# mainboard_v03_eurobot2014_r1.net
KiCad netlist of a schematic drawn in EAGLE
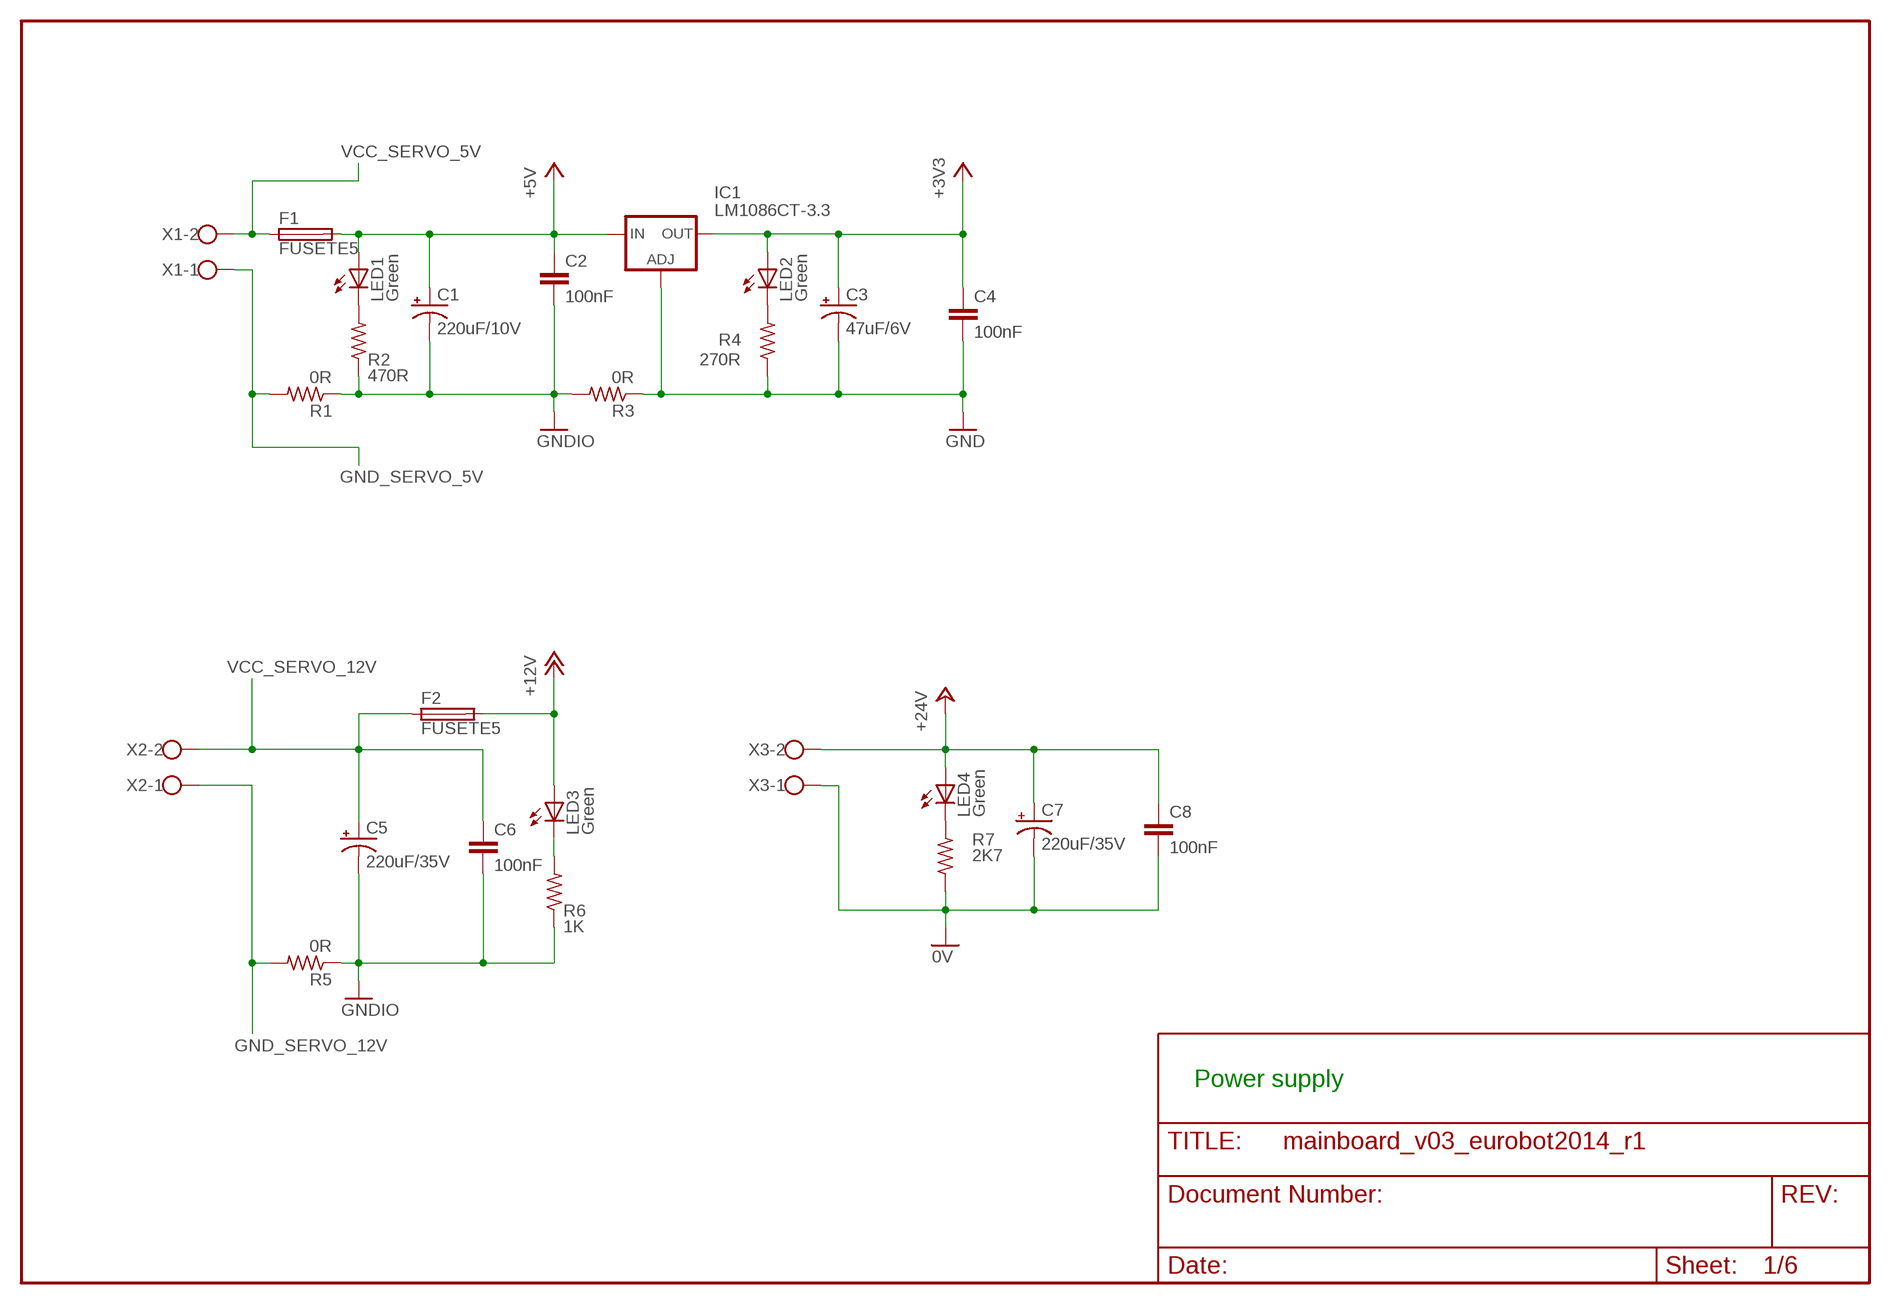
[diagram p0: schematic, sheet 1]
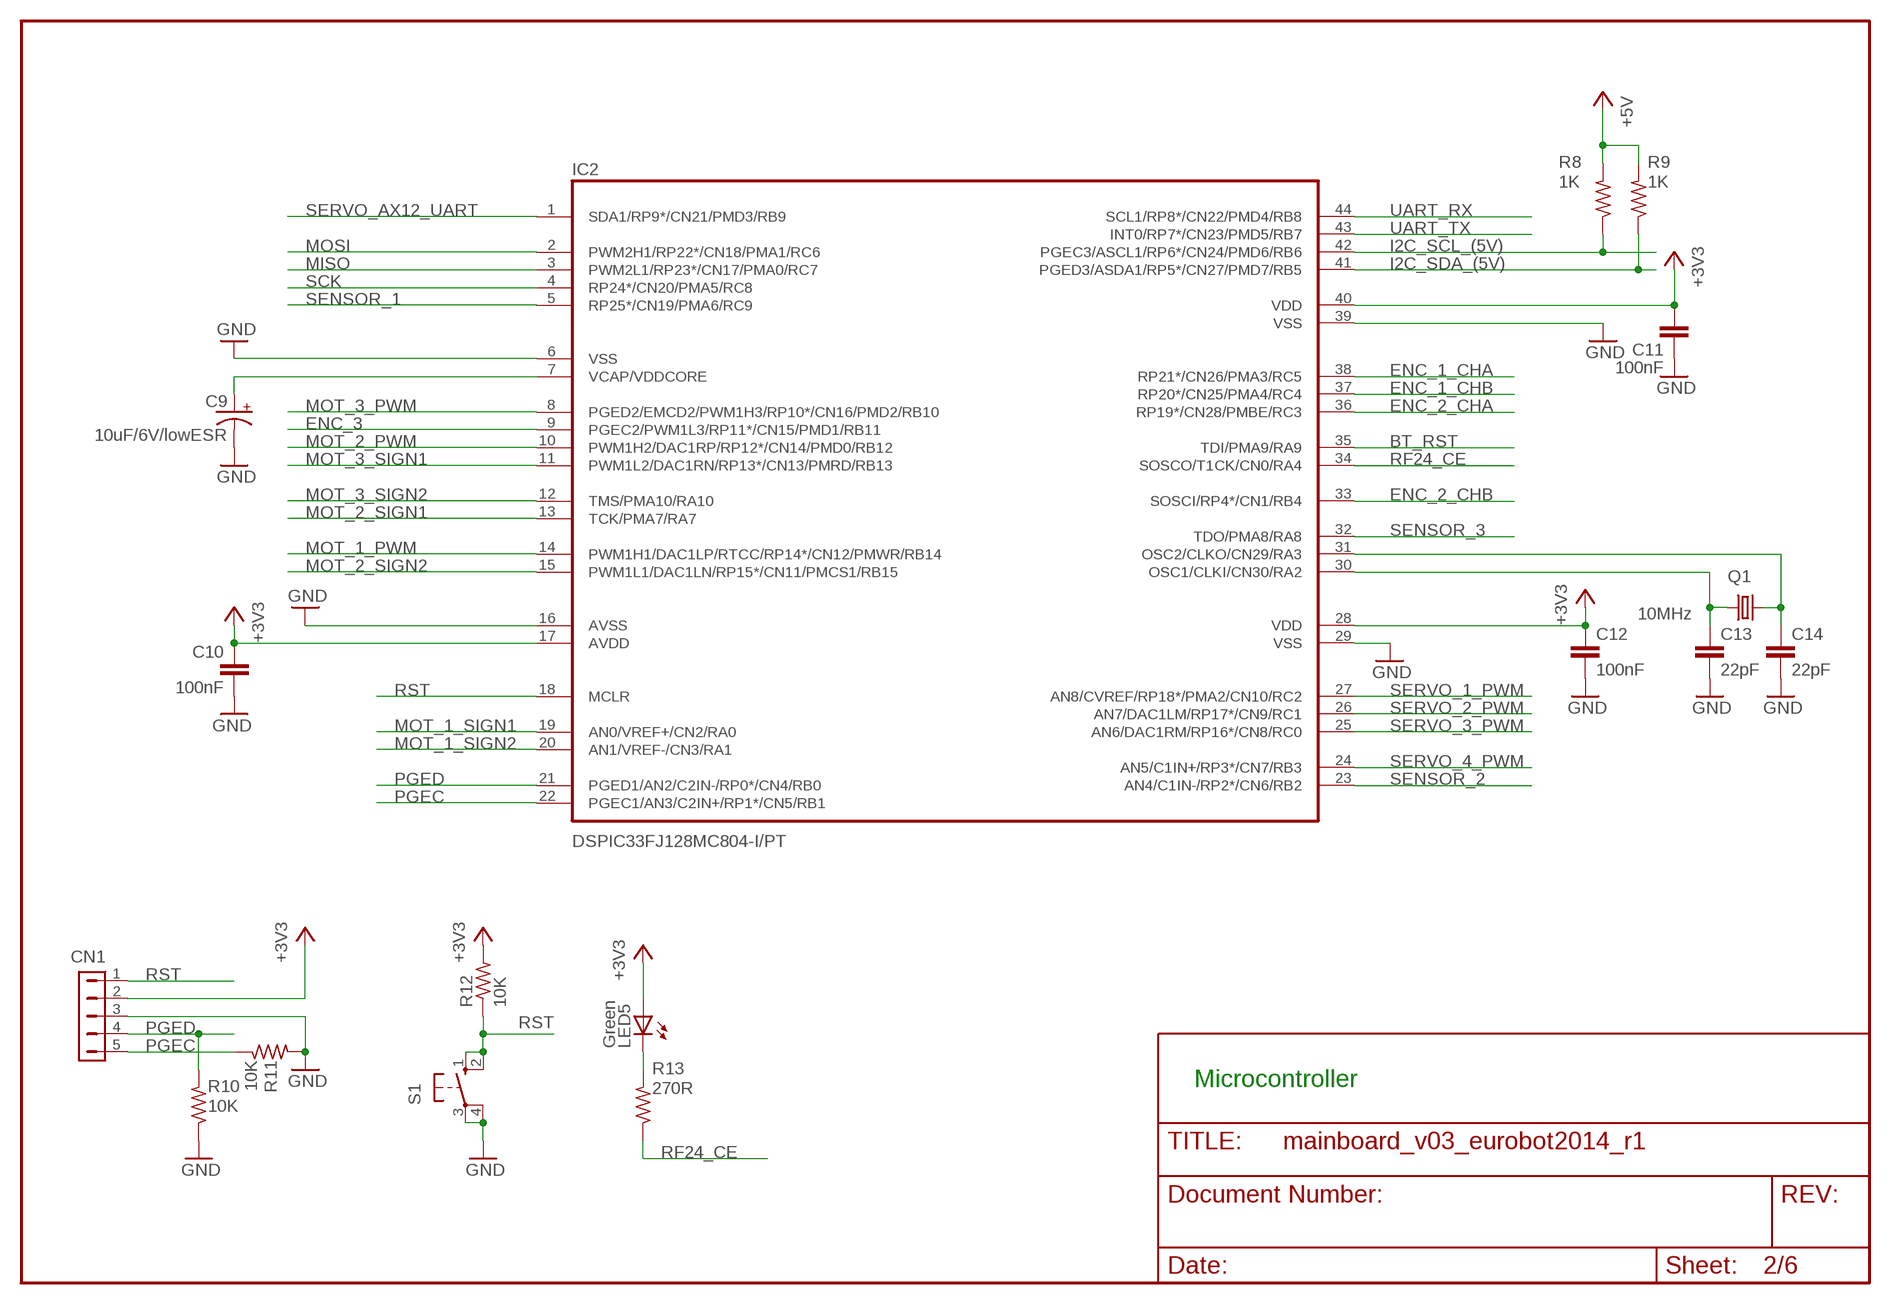
[diagram p1: schematic, sheet 2]
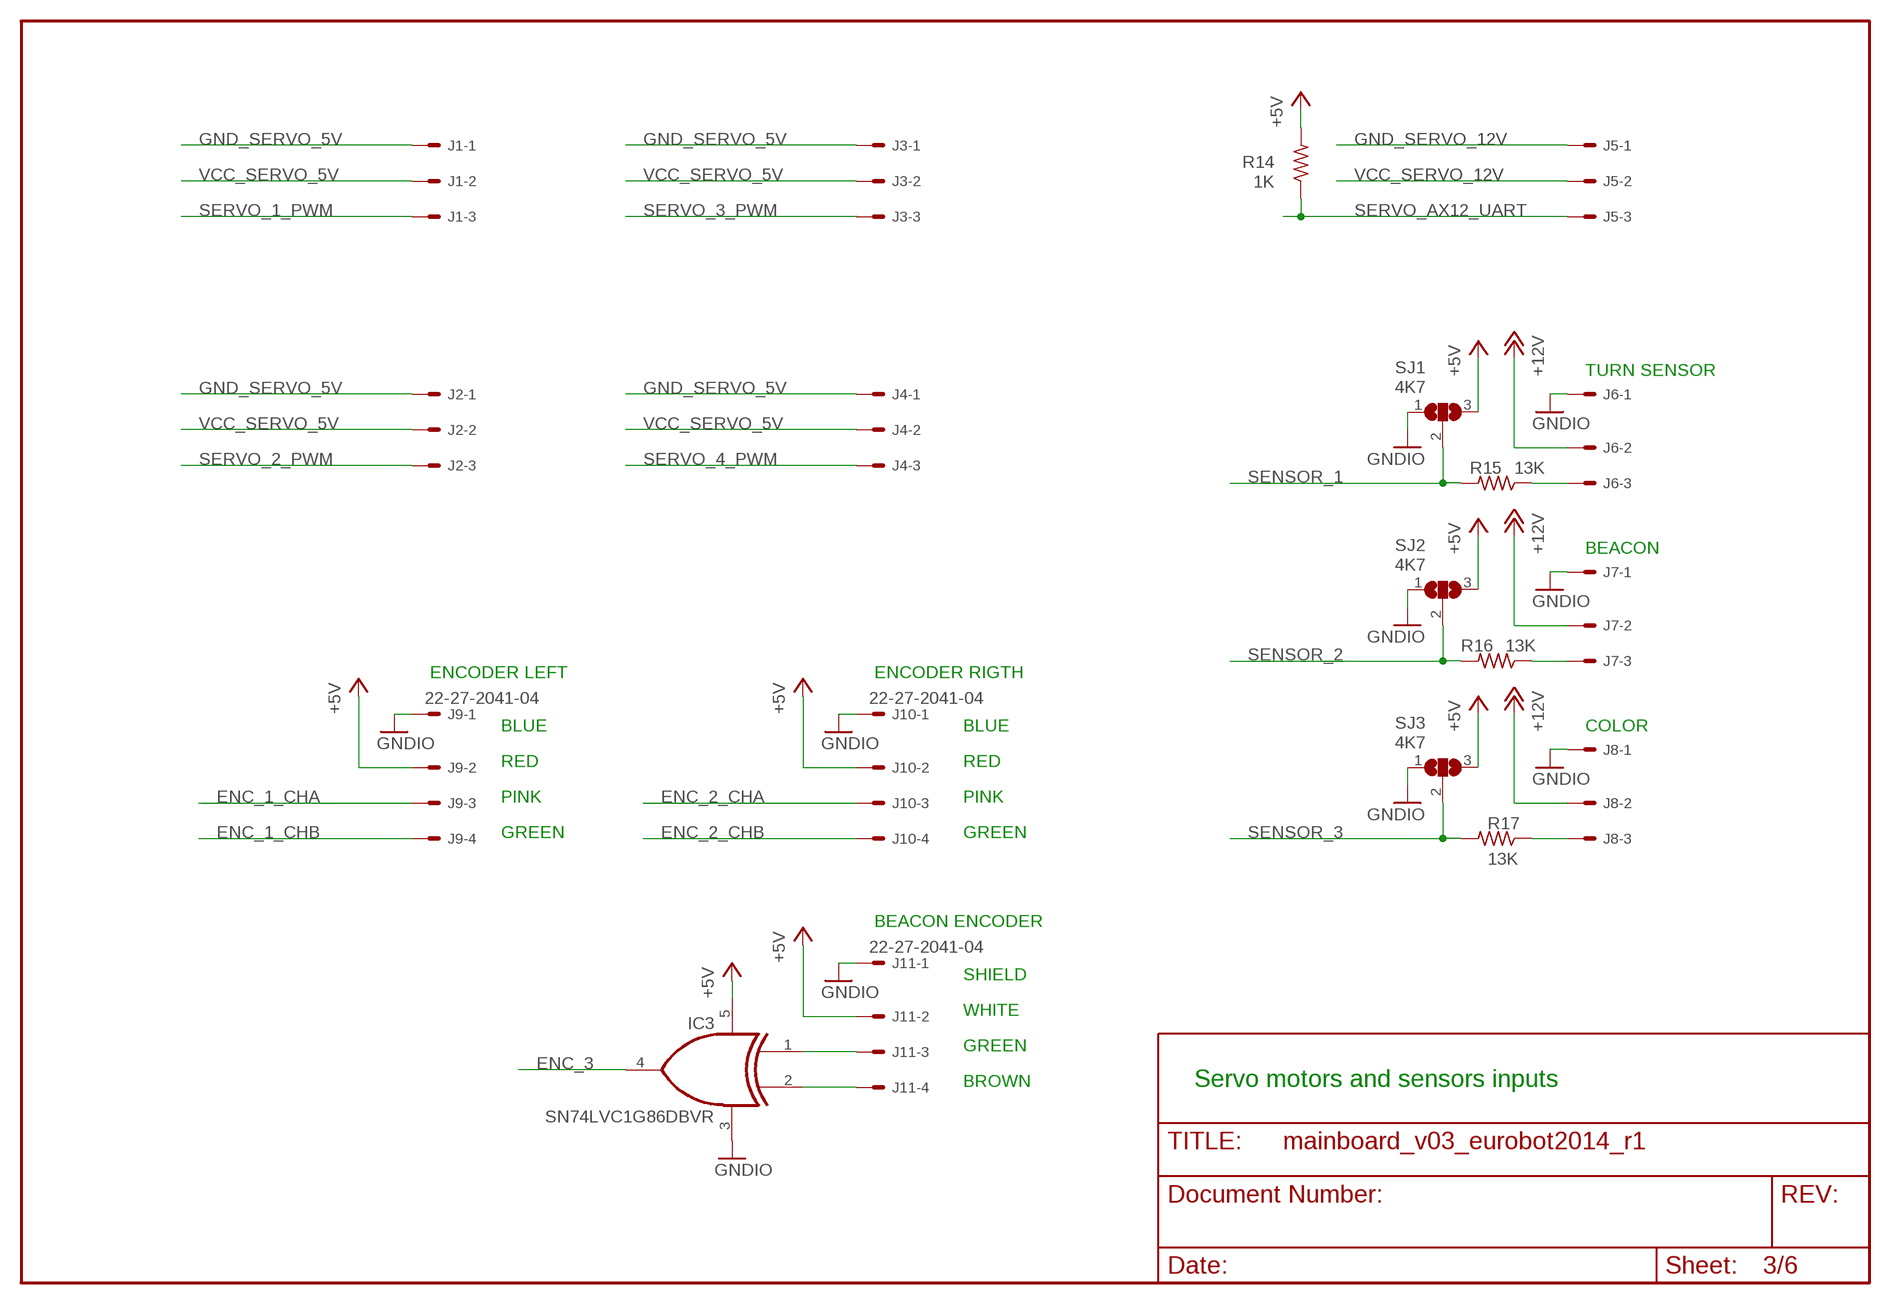
[diagram p2: schematic, sheet 3]
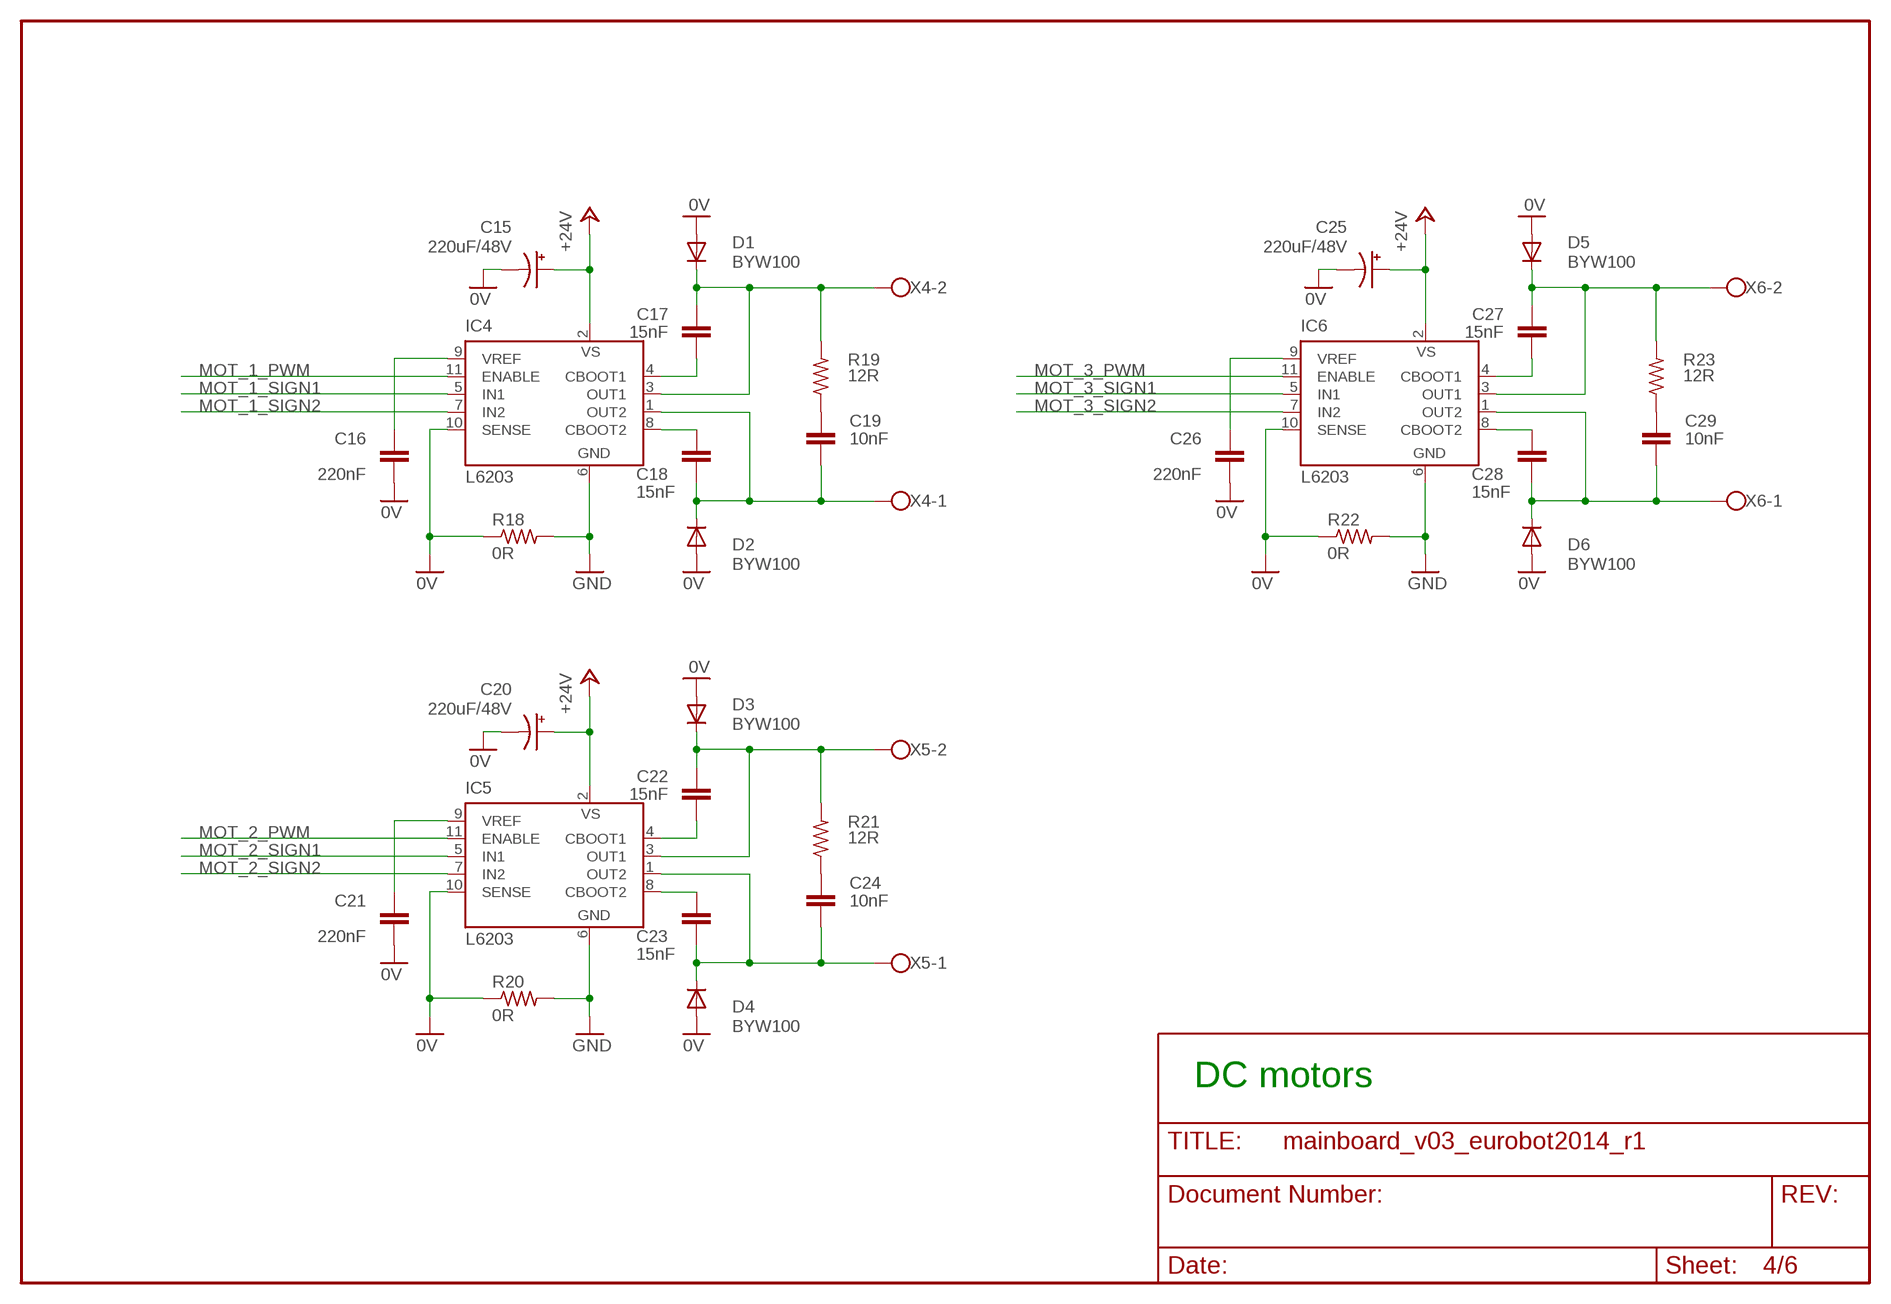
[diagram p3: schematic, sheet 4]
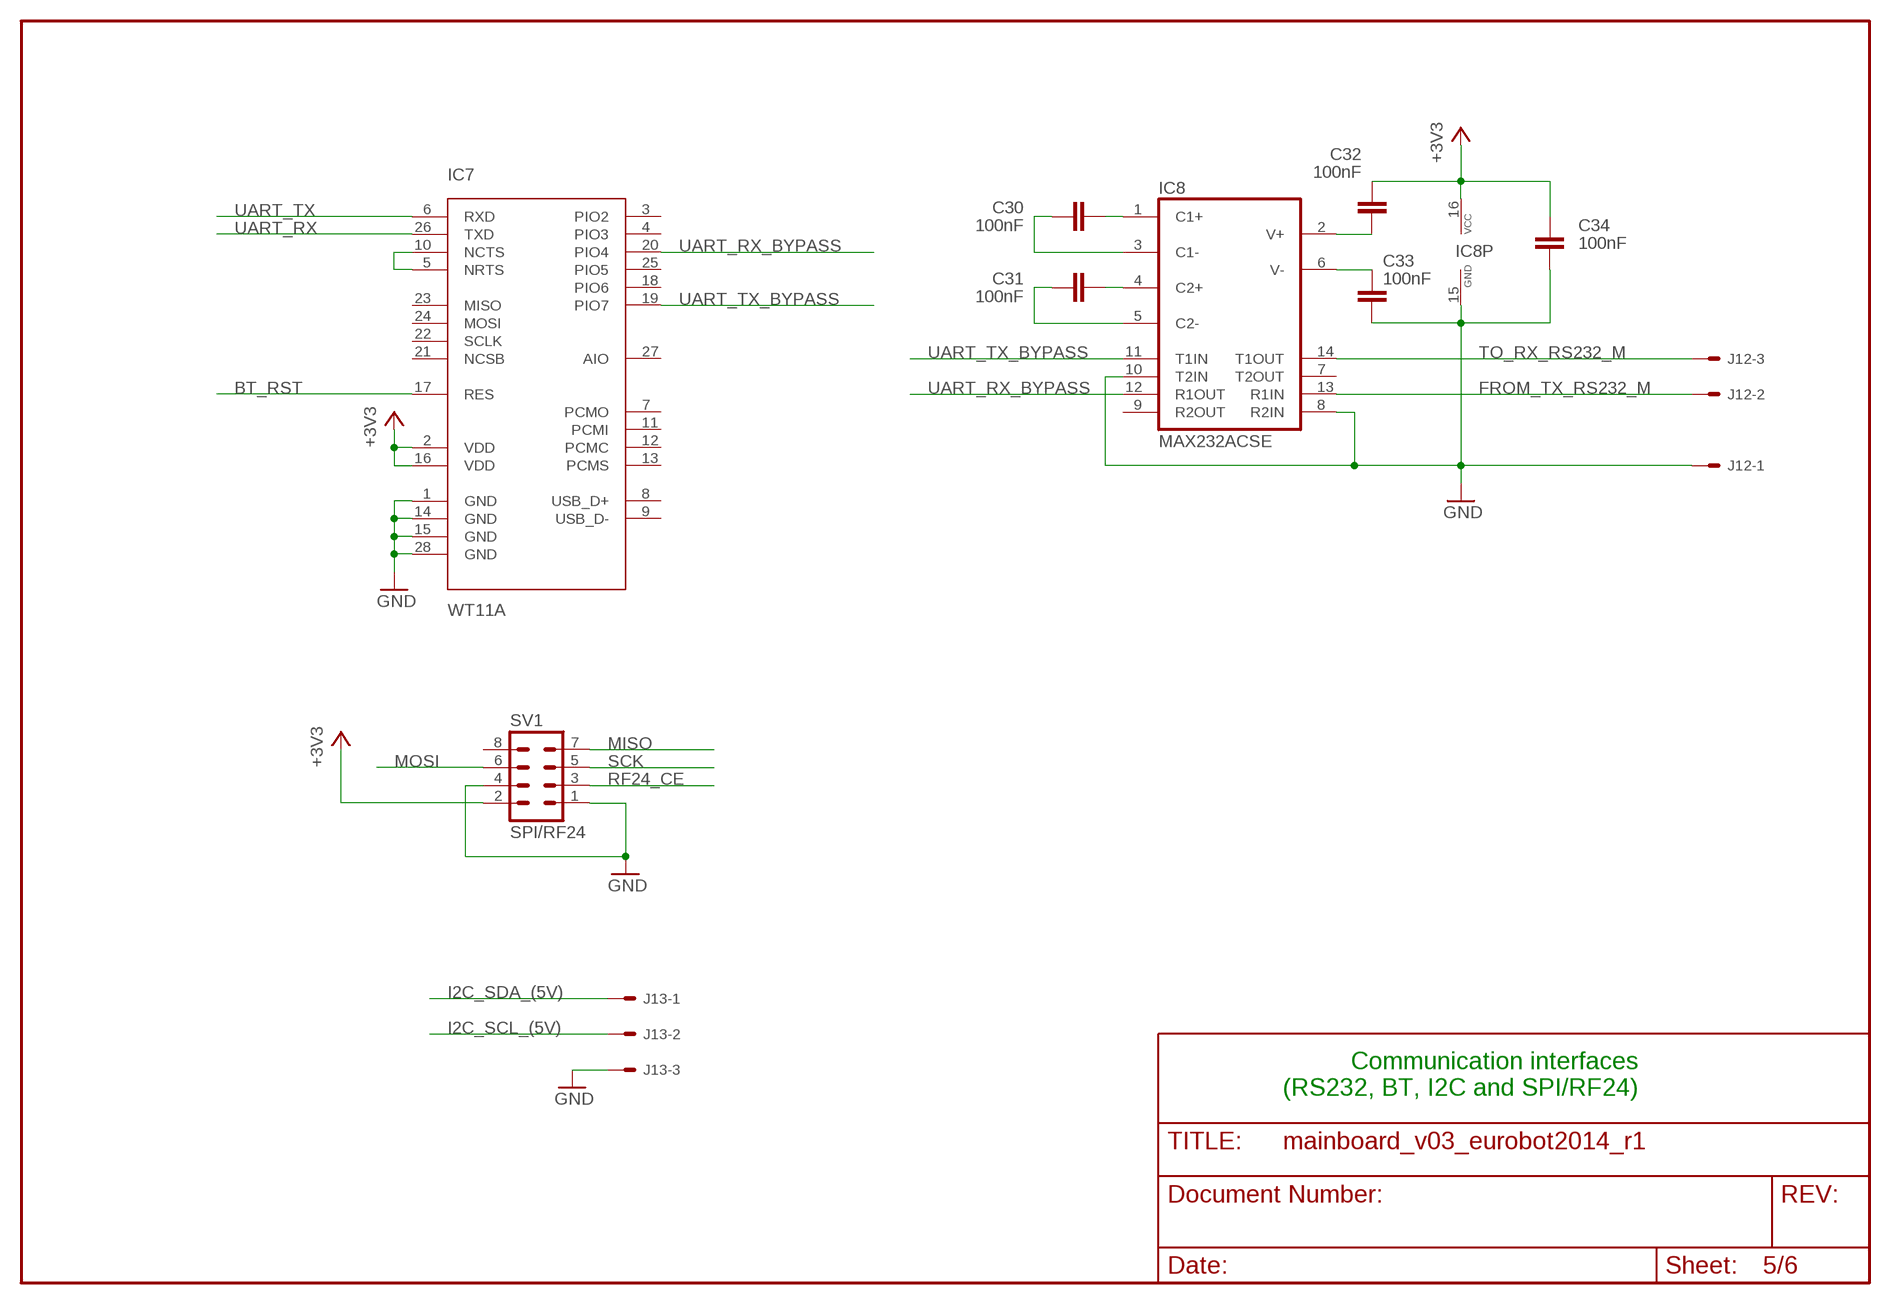
[diagram p4: schematic, sheet 5]
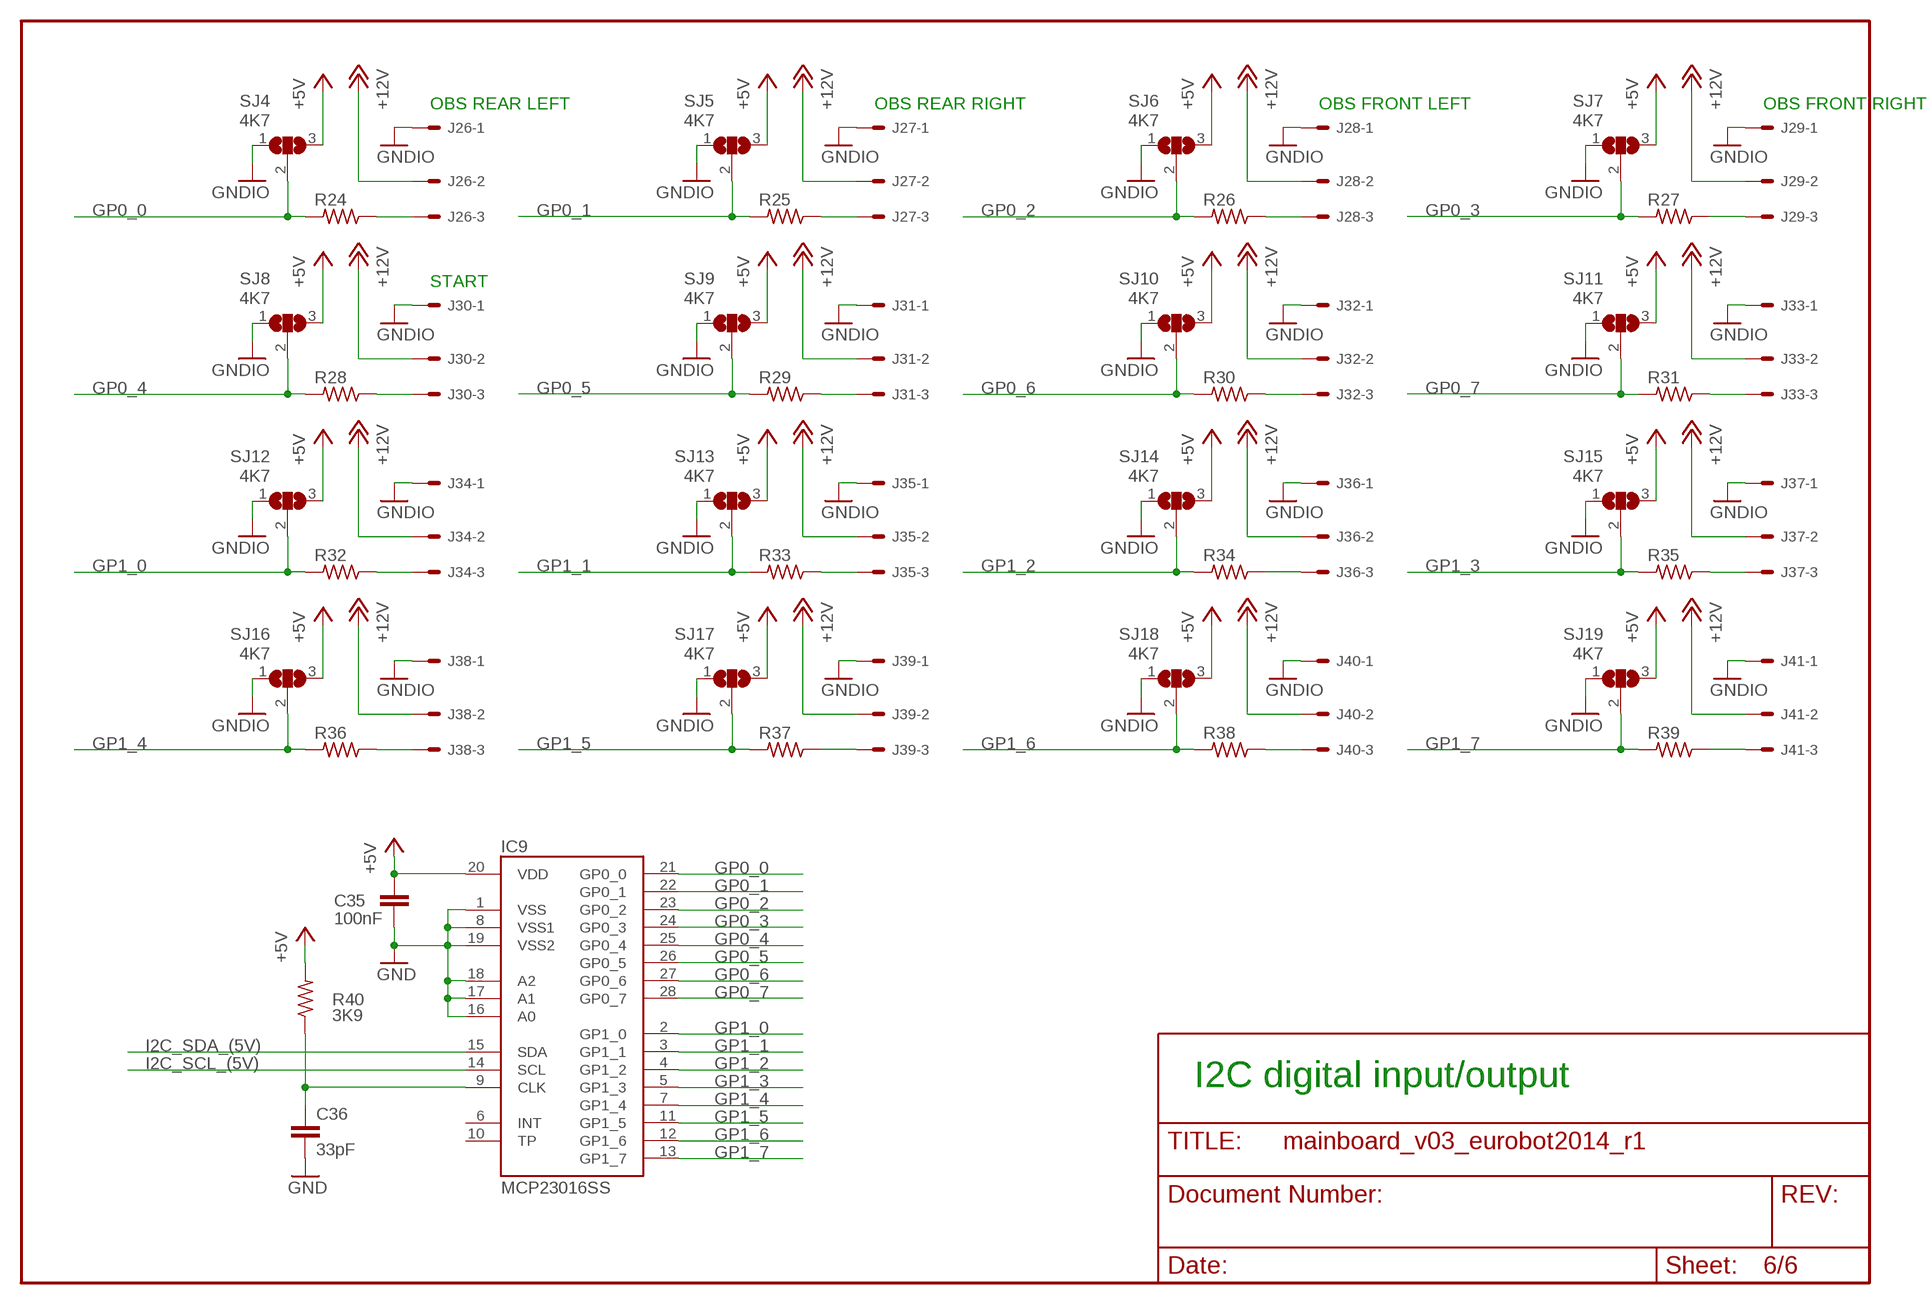
[diagram p5: schematic, sheet 6]

(export (version "E")
  (design (tool "Eeschema 10.0.6"))
  (components
    (comp (ref "C35")
      (value "100nF")
      (footprint "eagle-import:C0805")
      (libsource (lib "eagle-import") (part "C-EUC0805"))
    )
    (comp (ref "C36")
      (value "33pF")
      (footprint "eagle-import:C0805")
      (libsource (lib "eagle-import") (part "C-EUC0805"))
    )
    (comp (ref "IC9")
      (value "MCP23016SS")
      (footprint "eagle-import:SSOP28")
      (libsource (lib "eagle-import") (part "MCP23016SS"))
    )
    (comp (ref "J26")
      (value "22-27-2031-03")
      (footprint "eagle-import:6410-03")
      (libsource (lib "eagle-import") (part "22-?-0327-2031"))
    )
    (comp (ref "J27")
      (value "22-27-2031-03")
      (footprint "eagle-import:6410-03")
      (libsource (lib "eagle-import") (part "22-?-0327-2031"))
    )
    (comp (ref "J28")
      (value "22-27-2031-03")
      (footprint "eagle-import:6410-03")
      (libsource (lib "eagle-import") (part "22-?-0327-2031"))
    )
    (comp (ref "J29")
      (value "22-27-2031-03")
      (footprint "eagle-import:6410-03")
      (libsource (lib "eagle-import") (part "22-?-0327-2031"))
    )
    (comp (ref "J30")
      (value "22-27-2031-03")
      (footprint "eagle-import:6410-03")
      (libsource (lib "eagle-import") (part "22-?-0327-2031"))
    )
    (comp (ref "J31")
      (value "22-27-2031-03")
      (footprint "eagle-import:6410-03")
      (libsource (lib "eagle-import") (part "22-?-0327-2031"))
    )
    (comp (ref "J32")
      (value "22-27-2031-03")
      (footprint "eagle-import:6410-03")
      (libsource (lib "eagle-import") (part "22-?-0327-2031"))
    )
    (comp (ref "J33")
      (value "22-27-2031-03")
      (footprint "eagle-import:6410-03")
      (libsource (lib "eagle-import") (part "22-?-0327-2031"))
    )
    (comp (ref "J34")
      (value "22-27-2031-03")
      (footprint "eagle-import:6410-03")
      (libsource (lib "eagle-import") (part "22-?-0327-2031"))
    )
    (comp (ref "J35")
      (value "22-27-2031-03")
      (footprint "eagle-import:6410-03")
      (libsource (lib "eagle-import") (part "22-?-0327-2031"))
    )
    (comp (ref "J36")
      (value "22-27-2031-03")
      (footprint "eagle-import:6410-03")
      (libsource (lib "eagle-import") (part "22-?-0327-2031"))
    )
    (comp (ref "J37")
      (value "22-27-2031-03")
      (footprint "eagle-import:6410-03")
      (libsource (lib "eagle-import") (part "22-?-0327-2031"))
    )
    (comp (ref "J38")
      (value "22-27-2031-03")
      (footprint "eagle-import:6410-03")
      (libsource (lib "eagle-import") (part "22-?-0327-2031"))
    )
    (comp (ref "J39")
      (value "22-27-2031-03")
      (footprint "eagle-import:6410-03")
      (libsource (lib "eagle-import") (part "22-?-0327-2031"))
    )
    (comp (ref "J40")
      (value "22-27-2031-03")
      (footprint "eagle-import:6410-03")
      (libsource (lib "eagle-import") (part "22-?-0327-2031"))
    )
    (comp (ref "J41")
      (value "22-27-2031-03")
      (footprint "eagle-import:6410-03")
      (libsource (lib "eagle-import") (part "22-?-0327-2031"))
    )
    (comp (ref "R24")
      (value "R-US_R0805")
      (footprint "eagle-import:R0805")
      (libsource (lib "eagle-import") (part "R-US_R0805"))
    )
    (comp (ref "R25")
      (value "R-US_R0805")
      (footprint "eagle-import:R0805")
      (libsource (lib "eagle-import") (part "R-US_R0805"))
    )
    (comp (ref "R26")
      (value "R-US_R0805")
      (footprint "eagle-import:R0805")
      (libsource (lib "eagle-import") (part "R-US_R0805"))
    )
    (comp (ref "R27")
      (value "R-US_R0805")
      (footprint "eagle-import:R0805")
      (libsource (lib "eagle-import") (part "R-US_R0805"))
    )
    (comp (ref "R28")
      (value "R-US_R0805")
      (footprint "eagle-import:R0805")
      (libsource (lib "eagle-import") (part "R-US_R0805"))
    )
    (comp (ref "R29")
      (value "R-US_R0805")
      (footprint "eagle-import:R0805")
      (libsource (lib "eagle-import") (part "R-US_R0805"))
    )
    (comp (ref "R30")
      (value "R-US_R0805")
      (footprint "eagle-import:R0805")
      (libsource (lib "eagle-import") (part "R-US_R0805"))
    )
    (comp (ref "R31")
      (value "R-US_R0805")
      (footprint "eagle-import:R0805")
      (libsource (lib "eagle-import") (part "R-US_R0805"))
    )
    (comp (ref "R32")
      (value "R-US_R0805")
      (footprint "eagle-import:R0805")
      (libsource (lib "eagle-import") (part "R-US_R0805"))
    )
    (comp (ref "R33")
      (value "R-US_R0805")
      (footprint "eagle-import:R0805")
      (libsource (lib "eagle-import") (part "R-US_R0805"))
    )
    (comp (ref "R34")
      (value "R-US_R0805")
      (footprint "eagle-import:R0805")
      (libsource (lib "eagle-import") (part "R-US_R0805"))
    )
    (comp (ref "R35")
      (value "R-US_R0805")
      (footprint "eagle-import:R0805")
      (libsource (lib "eagle-import") (part "R-US_R0805"))
    )
    (comp (ref "R36")
      (value "R-US_R0805")
      (footprint "eagle-import:R0805")
      (libsource (lib "eagle-import") (part "R-US_R0805"))
    )
    (comp (ref "R37")
      (value "R-US_R0805")
      (footprint "eagle-import:R0805")
      (libsource (lib "eagle-import") (part "R-US_R0805"))
    )
    (comp (ref "R38")
      (value "R-US_R0805")
      (footprint "eagle-import:R0805")
      (libsource (lib "eagle-import") (part "R-US_R0805"))
    )
    (comp (ref "R39")
      (value "R-US_R0805")
      (footprint "eagle-import:R0805")
      (libsource (lib "eagle-import") (part "R-US_R0805"))
    )
    (comp (ref "R40")
      (value "3K9")
      (footprint "eagle-import:R0805")
      (libsource (lib "eagle-import") (part "R-US_R0805"))
    )
    (comp (ref "SJ4")
      (value "4K7")
      (footprint "eagle-import:SJ_2")
      (libsource (lib "eagle-import") (part "SJ2W"))
    )
    (comp (ref "SJ5")
      (value "4K7")
      (footprint "eagle-import:SJ_2")
      (libsource (lib "eagle-import") (part "SJ2W"))
    )
    (comp (ref "SJ6")
      (value "4K7")
      (footprint "eagle-import:SJ_2")
      (libsource (lib "eagle-import") (part "SJ2W"))
    )
    (comp (ref "SJ7")
      (value "4K7")
      (footprint "eagle-import:SJ_2")
      (libsource (lib "eagle-import") (part "SJ2W"))
    )
    (comp (ref "SJ8")
      (value "4K7")
      (footprint "eagle-import:SJ_2")
      (libsource (lib "eagle-import") (part "SJ2W"))
    )
    (comp (ref "SJ9")
      (value "4K7")
      (footprint "eagle-import:SJ_2")
      (libsource (lib "eagle-import") (part "SJ2W"))
    )
    (comp (ref "SJ10")
      (value "4K7")
      (footprint "eagle-import:SJ_2")
      (libsource (lib "eagle-import") (part "SJ2W"))
    )
    (comp (ref "SJ11")
      (value "4K7")
      (footprint "eagle-import:SJ_2")
      (libsource (lib "eagle-import") (part "SJ2W"))
    )
    (comp (ref "SJ12")
      (value "4K7")
      (footprint "eagle-import:SJ_2")
      (libsource (lib "eagle-import") (part "SJ2W"))
    )
    (comp (ref "SJ13")
      (value "4K7")
      (footprint "eagle-import:SJ_2")
      (libsource (lib "eagle-import") (part "SJ2W"))
    )
    (comp (ref "SJ14")
      (value "4K7")
      (footprint "eagle-import:SJ_2")
      (libsource (lib "eagle-import") (part "SJ2W"))
    )
    (comp (ref "SJ15")
      (value "4K7")
      (footprint "eagle-import:SJ_2")
      (libsource (lib "eagle-import") (part "SJ2W"))
    )
    (comp (ref "SJ16")
      (value "4K7")
      (footprint "eagle-import:SJ_2")
      (libsource (lib "eagle-import") (part "SJ2W"))
    )
    (comp (ref "SJ17")
      (value "4K7")
      (footprint "eagle-import:SJ_2")
      (libsource (lib "eagle-import") (part "SJ2W"))
    )
    (comp (ref "SJ18")
      (value "4K7")
      (footprint "eagle-import:SJ_2")
      (libsource (lib "eagle-import") (part "SJ2W"))
    )
    (comp (ref "SJ19")
      (value "4K7")
      (footprint "eagle-import:SJ_2")
      (libsource (lib "eagle-import") (part "SJ2W"))
    )
    (comp (ref "C1")
      (value "220uF/10V")
      (footprint "eagle-import:E2,5-7")
      (libsource (lib "eagle-import") (part "CPOL-USE2.5-7"))
    )
    (comp (ref "C2")
      (value "100nF")
      (footprint "eagle-import:C0805")
      (libsource (lib "eagle-import") (part "C-EUC0805"))
    )
    (comp (ref "C3")
      (value "47uF/6V")
      (footprint "eagle-import:SMC_D")
      (libsource (lib "eagle-import") (part "CPOL-USSMCD"))
    )
    (comp (ref "C4")
      (value "100nF")
      (footprint "eagle-import:C0805")
      (libsource (lib "eagle-import") (part "C-EUC0805"))
    )
    (comp (ref "C5")
      (value "220uF/35V")
      (footprint "eagle-import:E5-10,5")
      (libsource (lib "eagle-import") (part "CPOL-USE5-10.5"))
    )
    (comp (ref "C6")
      (value "100nF")
      (footprint "eagle-import:C0805")
      (libsource (lib "eagle-import") (part "C-EUC0805"))
    )
    (comp (ref "C7")
      (value "220uF/35V")
      (footprint "eagle-import:E5-10,5")
      (libsource (lib "eagle-import") (part "CPOL-USE5-10.5"))
    )
    (comp (ref "C8")
      (value "100nF")
      (footprint "eagle-import:C0805")
      (libsource (lib "eagle-import") (part "C-EUC0805"))
    )
    (comp (ref "F1")
      (value "FUSETE5")
      (footprint "eagle-import:TE5")
      (libsource (lib "eagle-import") (part "FUSETE5"))
    )
    (comp (ref "F2")
      (value "FUSETE5")
      (footprint "eagle-import:TE5")
      (libsource (lib "eagle-import") (part "FUSETE5"))
    )
    (comp (ref "IC1")
      (value "LM1086CT-3.3")
      (footprint "eagle-import:317TS")
      (libsource (lib "eagle-import") (part "LM317TS"))
    )
    (comp (ref "LED1")
      (value "Green")
      (footprint "eagle-import:CHIP-LED0805")
      (libsource (lib "eagle-import") (part "LEDCHIP-LED0805"))
    )
    (comp (ref "LED2")
      (value "Green")
      (footprint "eagle-import:CHIP-LED0805")
      (libsource (lib "eagle-import") (part "LEDCHIP-LED0805"))
    )
    (comp (ref "LED3")
      (value "Green")
      (footprint "eagle-import:CHIP-LED0805")
      (libsource (lib "eagle-import") (part "LEDCHIP-LED0805"))
    )
    (comp (ref "LED4")
      (value "Green")
      (footprint "eagle-import:CHIP-LED0805")
      (libsource (lib "eagle-import") (part "LEDCHIP-LED0805"))
    )
    (comp (ref "R1")
      (value "0R")
      (footprint "eagle-import:R0805")
      (libsource (lib "eagle-import") (part "R-US_R0805"))
    )
    (comp (ref "R2")
      (value "470R")
      (footprint "eagle-import:R0805")
      (libsource (lib "eagle-import") (part "R-US_R0805"))
    )
    (comp (ref "R3")
      (value "0R")
      (footprint "eagle-import:R0805")
      (libsource (lib "eagle-import") (part "R-US_R0805"))
    )
    (comp (ref "R4")
      (value "270R")
      (footprint "eagle-import:R0805")
      (libsource (lib "eagle-import") (part "R-US_R0805"))
    )
    (comp (ref "R5")
      (value "0R")
      (footprint "eagle-import:R0805")
      (libsource (lib "eagle-import") (part "R-US_R0805"))
    )
    (comp (ref "R6")
      (value "1K")
      (footprint "eagle-import:R0805")
      (libsource (lib "eagle-import") (part "R-US_R0805"))
    )
    (comp (ref "R7")
      (value "2K7")
      (footprint "eagle-import:R0805")
      (libsource (lib "eagle-import") (part "R-US_R0805"))
    )
    (comp (ref "X1")
      (value "W237-02P")
      (footprint "eagle-import:W237-132")
      (libsource (lib "eagle-import") (part "W237-02P"))
    )
    (comp (ref "X2")
      (value "W237-02P")
      (footprint "eagle-import:W237-132")
      (libsource (lib "eagle-import") (part "W237-02P"))
    )
    (comp (ref "X3")
      (value "W237-02P")
      (footprint "eagle-import:W237-132")
      (libsource (lib "eagle-import") (part "W237-02P"))
    )
    (comp (ref "C15")
      (value "220uF/48V")
      (footprint "eagle-import:E3,5-10")
      (libsource (lib "eagle-import") (part "CPOL-USE3.5-10"))
    )
    (comp (ref "C16")
      (value "220nF")
      (footprint "eagle-import:C0805")
      (libsource (lib "eagle-import") (part "C-EUC0805"))
    )
    (comp (ref "C17")
      (value "15nF")
      (footprint "eagle-import:C0805")
      (libsource (lib "eagle-import") (part "C-EUC0805"))
    )
    (comp (ref "C18")
      (value "15nF")
      (footprint "eagle-import:C0805")
      (libsource (lib "eagle-import") (part "C-EUC0805"))
    )
    (comp (ref "C19")
      (value "10nF")
      (footprint "eagle-import:C0805")
      (libsource (lib "eagle-import") (part "C-EUC0805"))
    )
    (comp (ref "C20")
      (value "220uF/48V")
      (footprint "eagle-import:E3,5-10")
      (libsource (lib "eagle-import") (part "CPOL-USE3.5-10"))
    )
    (comp (ref "C21")
      (value "220nF")
      (footprint "eagle-import:C0805")
      (libsource (lib "eagle-import") (part "C-EUC0805"))
    )
    (comp (ref "C22")
      (value "15nF")
      (footprint "eagle-import:C0805")
      (libsource (lib "eagle-import") (part "C-EUC0805"))
    )
    (comp (ref "C23")
      (value "15nF")
      (footprint "eagle-import:C0805")
      (libsource (lib "eagle-import") (part "C-EUC0805"))
    )
    (comp (ref "C24")
      (value "10nF")
      (footprint "eagle-import:C0805")
      (libsource (lib "eagle-import") (part "C-EUC0805"))
    )
    (comp (ref "C25")
      (value "220uF/48V")
      (footprint "eagle-import:E3,5-10")
      (libsource (lib "eagle-import") (part "CPOL-USE3.5-10"))
    )
    (comp (ref "C26")
      (value "220nF")
      (footprint "eagle-import:C0805")
      (libsource (lib "eagle-import") (part "C-EUC0805"))
    )
    (comp (ref "C27")
      (value "15nF")
      (footprint "eagle-import:C0805")
      (libsource (lib "eagle-import") (part "C-EUC0805"))
    )
    (comp (ref "C28")
      (value "15nF")
      (footprint "eagle-import:C0805")
      (libsource (lib "eagle-import") (part "C-EUC0805"))
    )
    (comp (ref "C29")
      (value "10nF")
      (footprint "eagle-import:C0805")
      (libsource (lib "eagle-import") (part "C-EUC0805"))
    )
    (comp (ref "D1")
      (value "BYW100")
      (footprint "eagle-import:F126-10")
      (libsource (lib "eagle-import") (part "BYW100"))
    )
    (comp (ref "D2")
      (value "BYW100")
      (footprint "eagle-import:F126-10")
      (libsource (lib "eagle-import") (part "BYW100"))
    )
    (comp (ref "D3")
      (value "BYW100")
      (footprint "eagle-import:F126-10")
      (libsource (lib "eagle-import") (part "BYW100"))
    )
    (comp (ref "D4")
      (value "BYW100")
      (footprint "eagle-import:F126-10")
      (libsource (lib "eagle-import") (part "BYW100"))
    )
    (comp (ref "D5")
      (value "BYW100")
      (footprint "eagle-import:F126-10")
      (libsource (lib "eagle-import") (part "BYW100"))
    )
    (comp (ref "D6")
      (value "BYW100")
      (footprint "eagle-import:F126-10")
      (libsource (lib "eagle-import") (part "BYW100"))
    )
    (comp (ref "IC4")
      (value "L6203")
      (footprint "eagle-import:MULTIWATT-11")
      (libsource (lib "eagle-import") (part "L6203"))
    )
    (comp (ref "IC5")
      (value "L6203")
      (footprint "eagle-import:MULTIWATT-11")
      (libsource (lib "eagle-import") (part "L6203"))
    )
    (comp (ref "IC6")
      (value "L6203")
      (footprint "eagle-import:MULTIWATT-11")
      (libsource (lib "eagle-import") (part "L6203"))
    )
    (comp (ref "R18")
      (value "0R")
      (footprint "eagle-import:M0805")
      (libsource (lib "eagle-import") (part "R-US_M0805"))
    )
    (comp (ref "R19")
      (value "12R")
      (footprint "eagle-import:M0805")
      (libsource (lib "eagle-import") (part "R-US_M0805"))
    )
    (comp (ref "R20")
      (value "0R")
      (footprint "eagle-import:M0805")
      (libsource (lib "eagle-import") (part "R-US_M0805"))
    )
    (comp (ref "R21")
      (value "12R")
      (footprint "eagle-import:M0805")
      (libsource (lib "eagle-import") (part "R-US_M0805"))
    )
    (comp (ref "R22")
      (value "0R")
      (footprint "eagle-import:M0805")
      (libsource (lib "eagle-import") (part "R-US_M0805"))
    )
    (comp (ref "R23")
      (value "12R")
      (footprint "eagle-import:M0805")
      (libsource (lib "eagle-import") (part "R-US_M0805"))
    )
    (comp (ref "X4")
      (value "W237-02P")
      (footprint "eagle-import:W237-132")
      (libsource (lib "eagle-import") (part "W237-02P"))
    )
    (comp (ref "X5")
      (value "W237-02P")
      (footprint "eagle-import:W237-132")
      (libsource (lib "eagle-import") (part "W237-02P"))
    )
    (comp (ref "X6")
      (value "W237-02P")
      (footprint "eagle-import:W237-132")
      (libsource (lib "eagle-import") (part "W237-02P"))
    )
    (comp (ref "C9")
      (value "10uF/6V/lowESR")
      (footprint "eagle-import:SMC_A")
      (libsource (lib "eagle-import") (part "CPOL-USSMCA"))
    )
    (comp (ref "C10")
      (value "100nF")
      (footprint "eagle-import:C0603")
      (libsource (lib "eagle-import") (part "C-EUC0603"))
    )
    (comp (ref "C11")
      (value "100nF")
      (footprint "eagle-import:C0603")
      (libsource (lib "eagle-import") (part "C-EUC0603"))
    )
    (comp (ref "C12")
      (value "100nF")
      (footprint "eagle-import:C0603")
      (libsource (lib "eagle-import") (part "C-EUC0603"))
    )
    (comp (ref "C13")
      (value "22pF")
      (footprint "eagle-import:C0805")
      (libsource (lib "eagle-import") (part "C-EUC0805"))
    )
    (comp (ref "C14")
      (value "22pF")
      (footprint "eagle-import:C0805")
      (libsource (lib "eagle-import") (part "C-EUC0805"))
    )
    (comp (ref "CN1")
      (value "HDR-1X5-SIP-100")
      (footprint "eagle-import:SIP-100-5V")
      (libsource (lib "eagle-import") (part "HDR-1X5-SIP-100"))
    )
    (comp (ref "IC2")
      (value "DSPIC33FJ128MC804-I/PT")
      (footprint "eagle-import:TQFP44")
      (libsource (lib "eagle-import") (part "DSPIC33FJXXMC804SMD"))
    )
    (comp (ref "LED5")
      (value "Green")
      (footprint "eagle-import:CHIP-LED0805")
      (libsource (lib "eagle-import") (part "LEDCHIP-LED0805"))
    )
    (comp (ref "Q1")
      (value "10MHz")
      (footprint "eagle-import:HC49UP")
      (libsource (lib "eagle-import") (part "CRYSTALHC49UP"))
    )
    (comp (ref "R8")
      (value "1K")
      (footprint "eagle-import:R0805")
      (libsource (lib "eagle-import") (part "R-US_R0805"))
    )
    (comp (ref "R9")
      (value "1K")
      (footprint "eagle-import:R0805")
      (libsource (lib "eagle-import") (part "R-US_R0805"))
    )
    (comp (ref "R10")
      (value "10K")
      (footprint "eagle-import:R0805")
      (libsource (lib "eagle-import") (part "R-US_R0805"))
    )
    (comp (ref "R11")
      (value "10K")
      (footprint "eagle-import:R0805")
      (libsource (lib "eagle-import") (part "R-US_R0805"))
    )
    (comp (ref "R12")
      (value "10K")
      (footprint "eagle-import:R0805")
      (libsource (lib "eagle-import") (part "R-US_R0805"))
    )
    (comp (ref "R13")
      (value "270R")
      (footprint "eagle-import:R0805")
      (libsource (lib "eagle-import") (part "R-US_R0805"))
    )
    (comp (ref "S1")
      (value "10-XX")
      (footprint "eagle-import:B3F-10XX")
      (libsource (lib "eagle-import") (part "10-XX"))
    )
    (comp (ref "C30")
      (value "100nF")
      (footprint "eagle-import:C0603")
      (libsource (lib "eagle-import") (part "C-EUC0603"))
    )
    (comp (ref "C31")
      (value "100nF")
      (footprint "eagle-import:C0603")
      (libsource (lib "eagle-import") (part "C-EUC0603"))
    )
    (comp (ref "C32")
      (value "100nF")
      (footprint "eagle-import:C0603")
      (libsource (lib "eagle-import") (part "C-EUC0603"))
    )
    (comp (ref "C33")
      (value "100nF")
      (footprint "eagle-import:C0603")
      (libsource (lib "eagle-import") (part "C-EUC0603"))
    )
    (comp (ref "C34")
      (value "100nF")
      (footprint "eagle-import:C0603")
      (libsource (lib "eagle-import") (part "C-EUC0603"))
    )
    (comp (ref "IC7")
      (value "WT11A")
      (footprint "eagle-import:WT11")
      (libsource (lib "eagle-import") (part "WT11A"))
    )
    (comp (ref "IC8")
      (value "MAX232ACSE")
      (footprint "eagle-import:SO16")
      (libsource (lib "eagle-import") (part "MAX232SEAC"))
    )
    (comp (ref "J12")
      (value "22-27-2031-03")
      (footprint "eagle-import:6410-03")
      (libsource (lib "eagle-import") (part "22-?-0327-2031"))
    )
    (comp (ref "J13")
      (value "22-27-2031-03")
      (footprint "eagle-import:6410-03")
      (libsource (lib "eagle-import") (part "22-?-0327-2031"))
    )
    (comp (ref "SV1")
      (value "SPI/RF24")
      (footprint "eagle-import:MA04-2")
      (libsource (lib "eagle-import") (part "MA04-2"))
    )
    (comp (ref "IC3")
      (value "SN74LVC1G86DBVR")
      (footprint "eagle-import:SOT23-5")
      (libsource (lib "eagle-import") (part "741G86DBVAHC"))
    )
    (comp (ref "J1")
      (value "22-27-2031-03")
      (footprint "eagle-import:6410-03")
      (libsource (lib "eagle-import") (part "22-?-0327-2031"))
    )
    (comp (ref "J2")
      (value "22-27-2031-03")
      (footprint "eagle-import:6410-03")
      (libsource (lib "eagle-import") (part "22-?-0327-2031"))
    )
    (comp (ref "J3")
      (value "22-27-2031-03")
      (footprint "eagle-import:6410-03")
      (libsource (lib "eagle-import") (part "22-?-0327-2031"))
    )
    (comp (ref "J4")
      (value "22-27-2031-03")
      (footprint "eagle-import:6410-03")
      (libsource (lib "eagle-import") (part "22-?-0327-2031"))
    )
    (comp (ref "J5")
      (value "22-27-2031-03")
      (footprint "eagle-import:6410-03")
      (libsource (lib "eagle-import") (part "22-?-0327-2031"))
    )
    (comp (ref "J6")
      (value "22-27-2031-03")
      (footprint "eagle-import:6410-03")
      (libsource (lib "eagle-import") (part "22-?-0327-2031"))
    )
    (comp (ref "J7")
      (value "22-27-2031-03")
      (footprint "eagle-import:6410-03")
      (libsource (lib "eagle-import") (part "22-?-0327-2031"))
    )
    (comp (ref "J8")
      (value "22-27-2031-03")
      (footprint "eagle-import:6410-03")
      (libsource (lib "eagle-import") (part "22-?-0327-2031"))
    )
    (comp (ref "J9")
      (value "22-27-2041-04")
      (footprint "eagle-import:6410-04")
      (libsource (lib "eagle-import") (part "22-?-0427-2041"))
    )
    (comp (ref "J10")
      (value "22-27-2041-04")
      (footprint "eagle-import:6410-04")
      (libsource (lib "eagle-import") (part "22-?-0427-2041"))
    )
    (comp (ref "J11")
      (value "22-27-2041-04")
      (footprint "eagle-import:6410-04")
      (libsource (lib "eagle-import") (part "22-?-0427-2041"))
    )
    (comp (ref "R14")
      (value "1K")
      (footprint "eagle-import:R0805")
      (libsource (lib "eagle-import") (part "R-US_R0805"))
    )
    (comp (ref "R15")
      (value "13K")
      (footprint "eagle-import:R0805")
      (libsource (lib "eagle-import") (part "R-US_R0805"))
    )
    (comp (ref "R16")
      (value "13K")
      (footprint "eagle-import:R0805")
      (libsource (lib "eagle-import") (part "R-US_R0805"))
    )
    (comp (ref "R17")
      (value "13K")
      (footprint "eagle-import:R0805")
      (libsource (lib "eagle-import") (part "R-US_R0805"))
    )
    (comp (ref "SJ1")
      (value "4K7")
      (footprint "eagle-import:SJ_2")
      (libsource (lib "eagle-import") (part "SJ2W"))
    )
    (comp (ref "SJ2")
      (value "4K7")
      (footprint "eagle-import:SJ_2")
      (libsource (lib "eagle-import") (part "SJ2W"))
    )
    (comp (ref "SJ3")
      (value "4K7")
      (footprint "eagle-import:SJ_2")
      (libsource (lib "eagle-import") (part "SJ2W"))
    )
  )
  (nets
    (net (code "1") (name "+3V3") (class "Default")
      (node (ref "C10") (pin "1") (pinfunction "1_1") (pintype "passive"))
      (node (ref "C11") (pin "1") (pinfunction "1_1") (pintype "passive"))
      (node (ref "C12") (pin "1") (pinfunction "1_1") (pintype "passive"))
      (node (ref "C3") (pin "+") (pinfunction "+_+") (pintype "passive"))
      (node (ref "C32") (pin "2") (pinfunction "2_2") (pintype "passive"))
      (node (ref "C34") (pin "2") (pinfunction "2_2") (pintype "passive"))
      (node (ref "C4") (pin "1") (pinfunction "1_1") (pintype "passive"))
      (node (ref "CN1") (pin "2") (pinfunction "2_2") (pintype "passive"))
      (node (ref "IC1") (pin "2") (pinfunction "OUT_2") (pintype "passive"))
      (node (ref "IC2") (pin "17") (pinfunction "AVDD_17") (pintype "passive"))
      (node (ref "IC2") (pin "28") (pinfunction "VDD_28") (pintype "passive"))
      (node (ref "IC2") (pin "40") (pinfunction "VDD_40") (pintype "passive"))
      (node (ref "IC7") (pin "16") (pinfunction "VDD_16") (pintype "passive"))
      (node (ref "IC7") (pin "2") (pinfunction "VDD_2") (pintype "passive"))
      (node (ref "IC8") (pin "16") (pinfunction "VCC_16") (pintype "power_in"))
      (node (ref "LED2") (pin "A") (pinfunction "A_A") (pintype "passive"))
      (node (ref "LED5") (pin "A") (pinfunction "A_A") (pintype "passive"))
      (node (ref "R12") (pin "2") (pinfunction "2_2") (pintype "passive"))
      (node (ref "SV1") (pin "2") (pinfunction "2_2") (pintype "passive"))
    )
    (net (code "2") (name "+5V") (class "Default")
      (node (ref "C1") (pin "+") (pinfunction "+_+") (pintype "passive"))
      (node (ref "C2") (pin "1") (pinfunction "1_1") (pintype "passive"))
      (node (ref "C35") (pin "1") (pinfunction "1_1") (pintype "passive"))
      (node (ref "F1") (pin "2") (pinfunction "2_2") (pintype "passive"))
      (node (ref "IC1") (pin "3") (pinfunction "IN_3") (pintype "input"))
      (node (ref "IC3") (pin "5") (pinfunction "VCC_5") (pintype "power_in"))
      (node (ref "IC9") (pin "20") (pinfunction "VDD_20") (pintype "power_in"))
      (node (ref "J10") (pin "2") (pinfunction "S_2") (pintype "passive"))
      (node (ref "J11") (pin "2") (pinfunction "S_2") (pintype "passive"))
      (node (ref "J9") (pin "2") (pinfunction "S_2") (pintype "passive"))
      (node (ref "LED1") (pin "A") (pinfunction "A_A") (pintype "passive"))
      (node (ref "R14") (pin "2") (pinfunction "2_2") (pintype "passive"))
      (node (ref "R40") (pin "2") (pinfunction "2_2") (pintype "passive"))
      (node (ref "R8") (pin "2") (pinfunction "2_2") (pintype "passive"))
      (node (ref "R9") (pin "2") (pinfunction "2_2") (pintype "passive"))
      (node (ref "SJ1") (pin "3") (pinfunction "3_3") (pintype "passive"))
      (node (ref "SJ10") (pin "3") (pinfunction "3_3") (pintype "passive"))
      (node (ref "SJ11") (pin "3") (pinfunction "3_3") (pintype "passive"))
      (node (ref "SJ12") (pin "3") (pinfunction "3_3") (pintype "passive"))
      (node (ref "SJ13") (pin "3") (pinfunction "3_3") (pintype "passive"))
      (node (ref "SJ14") (pin "3") (pinfunction "3_3") (pintype "passive"))
      (node (ref "SJ15") (pin "3") (pinfunction "3_3") (pintype "passive"))
      (node (ref "SJ16") (pin "3") (pinfunction "3_3") (pintype "passive"))
      (node (ref "SJ17") (pin "3") (pinfunction "3_3") (pintype "passive"))
      (node (ref "SJ18") (pin "3") (pinfunction "3_3") (pintype "passive"))
      (node (ref "SJ19") (pin "3") (pinfunction "3_3") (pintype "passive"))
      (node (ref "SJ2") (pin "3") (pinfunction "3_3") (pintype "passive"))
      (node (ref "SJ3") (pin "3") (pinfunction "3_3") (pintype "passive"))
      (node (ref "SJ4") (pin "3") (pinfunction "3_3") (pintype "passive"))
      (node (ref "SJ5") (pin "3") (pinfunction "3_3") (pintype "passive"))
      (node (ref "SJ6") (pin "3") (pinfunction "3_3") (pintype "passive"))
      (node (ref "SJ7") (pin "3") (pinfunction "3_3") (pintype "passive"))
      (node (ref "SJ8") (pin "3") (pinfunction "3_3") (pintype "passive"))
      (node (ref "SJ9") (pin "3") (pinfunction "3_3") (pintype "passive"))
    )
    (net (code "3") (name "+12V") (class "Default")
      (node (ref "F2") (pin "2") (pinfunction "2_2") (pintype "passive"))
      (node (ref "J26") (pin "2") (pinfunction "S_2") (pintype "passive"))
      (node (ref "J27") (pin "2") (pinfunction "S_2") (pintype "passive"))
      (node (ref "J28") (pin "2") (pinfunction "S_2") (pintype "passive"))
      (node (ref "J29") (pin "2") (pinfunction "S_2") (pintype "passive"))
      (node (ref "J30") (pin "2") (pinfunction "S_2") (pintype "passive"))
      (node (ref "J31") (pin "2") (pinfunction "S_2") (pintype "passive"))
      (node (ref "J32") (pin "2") (pinfunction "S_2") (pintype "passive"))
      (node (ref "J33") (pin "2") (pinfunction "S_2") (pintype "passive"))
      (node (ref "J34") (pin "2") (pinfunction "S_2") (pintype "passive"))
      (node (ref "J35") (pin "2") (pinfunction "S_2") (pintype "passive"))
      (node (ref "J36") (pin "2") (pinfunction "S_2") (pintype "passive"))
      (node (ref "J37") (pin "2") (pinfunction "S_2") (pintype "passive"))
      (node (ref "J38") (pin "2") (pinfunction "S_2") (pintype "passive"))
      (node (ref "J39") (pin "2") (pinfunction "S_2") (pintype "passive"))
      (node (ref "J40") (pin "2") (pinfunction "S_2") (pintype "passive"))
      (node (ref "J41") (pin "2") (pinfunction "S_2") (pintype "passive"))
      (node (ref "J6") (pin "2") (pinfunction "S_2") (pintype "passive"))
      (node (ref "J7") (pin "2") (pinfunction "S_2") (pintype "passive"))
      (node (ref "J8") (pin "2") (pinfunction "S_2") (pintype "passive"))
      (node (ref "LED3") (pin "A") (pinfunction "A_A") (pintype "passive"))
    )
    (net (code "4") (name "+24V") (class "Default")
      (node (ref "C15") (pin "+") (pinfunction "+_+") (pintype "passive"))
      (node (ref "C20") (pin "+") (pinfunction "+_+") (pintype "passive"))
      (node (ref "C25") (pin "+") (pinfunction "+_+") (pintype "passive"))
      (node (ref "C7") (pin "+") (pinfunction "+_+") (pintype "passive"))
      (node (ref "C8") (pin "1") (pinfunction "1_1") (pintype "passive"))
      (node (ref "IC4") (pin "2") (pinfunction "VS_2") (pintype "power_in"))
      (node (ref "IC5") (pin "2") (pinfunction "VS_2") (pintype "power_in"))
      (node (ref "IC6") (pin "2") (pinfunction "VS_2") (pintype "power_in"))
      (node (ref "LED4") (pin "A") (pinfunction "A_A") (pintype "passive"))
      (node (ref "X3") (pin "2") (pinfunction "KL_2") (pintype "passive"))
    )
    (net (code "5") (name "0V") (class "Default")
      (node (ref "C15") (pin "-") (pinfunction "-_-") (pintype "passive"))
      (node (ref "C16") (pin "2") (pinfunction "2_2") (pintype "passive"))
      (node (ref "C20") (pin "-") (pinfunction "-_-") (pintype "passive"))
      (node (ref "C21") (pin "2") (pinfunction "2_2") (pintype "passive"))
      (node (ref "C25") (pin "-") (pinfunction "-_-") (pintype "passive"))
      (node (ref "C26") (pin "2") (pinfunction "2_2") (pintype "passive"))
      (node (ref "C7") (pin "-") (pinfunction "-_-") (pintype "passive"))
      (node (ref "C8") (pin "2") (pinfunction "2_2") (pintype "passive"))
      (node (ref "D1") (pin "A") (pinfunction "A_A") (pintype "passive"))
      (node (ref "D2") (pin "A") (pinfunction "A_A") (pintype "passive"))
      (node (ref "D3") (pin "A") (pinfunction "A_A") (pintype "passive"))
      (node (ref "D4") (pin "A") (pinfunction "A_A") (pintype "passive"))
      (node (ref "D5") (pin "A") (pinfunction "A_A") (pintype "passive"))
      (node (ref "D6") (pin "A") (pinfunction "A_A") (pintype "passive"))
      (node (ref "IC4") (pin "10") (pinfunction "SENSE_10") (pintype "input"))
      (node (ref "IC5") (pin "10") (pinfunction "SENSE_10") (pintype "input"))
      (node (ref "IC6") (pin "10") (pinfunction "SENSE_10") (pintype "input"))
      (node (ref "R18") (pin "1") (pinfunction "1_1") (pintype "passive"))
      (node (ref "R20") (pin "1") (pinfunction "1_1") (pintype "passive"))
      (node (ref "R22") (pin "1") (pinfunction "1_1") (pintype "passive"))
      (node (ref "R7") (pin "1") (pinfunction "1_1") (pintype "passive"))
      (node (ref "X3") (pin "1") (pinfunction "KL_1") (pintype "passive"))
    )
    (net (code "6") (name "BT_RST") (class "Default")
      (node (ref "IC2") (pin "35") (pinfunction "TDI/PMA9/RA9_35") (pintype "passive"))
      (node (ref "IC7") (pin "17") (pinfunction "RES_17") (pintype "passive"))
    )
    (net (code "7") (name "ENC_1_CHA") (class "Default")
      (node (ref "IC2") (pin "38") (pinfunction "RP21*/CN26/PMA3/RC5_38") (pintype "passive"))
      (node (ref "J9") (pin "3") (pinfunction "S_3") (pintype "passive"))
    )
    (net (code "8") (name "ENC_1_CHB") (class "Default")
      (node (ref "IC2") (pin "37") (pinfunction "RP20*/CN25/PMA4/RC4_37") (pintype "passive"))
      (node (ref "J9") (pin "4") (pinfunction "S_4") (pintype "passive"))
    )
    (net (code "9") (name "ENC_2_CHA") (class "Default")
      (node (ref "IC2") (pin "36") (pinfunction "RP19*/CN28/PMBE/RC3_36") (pintype "passive"))
      (node (ref "J10") (pin "3") (pinfunction "S_3") (pintype "passive"))
    )
    (net (code "10") (name "ENC_2_CHB") (class "Default")
      (node (ref "IC2") (pin "33") (pinfunction "SOSCI/RP4*/CN1/RB4_33") (pintype "passive"))
      (node (ref "J10") (pin "4") (pinfunction "S_4") (pintype "passive"))
    )
    (net (code "11") (name "ENC_3") (class "Default")
      (node (ref "IC2") (pin "9") (pinfunction "PGEC2/PWM1L3/RP11*/CN15/PMD1/RB11_9") (pintype "passive"))
      (node (ref "IC3") (pin "4") (pinfunction "O_4") (pintype "output"))
    )
    (net (code "12") (name "FROM_TX_RS232_M") (class "Default")
      (node (ref "IC8") (pin "13") (pinfunction "R1IN_13") (pintype "input"))
      (node (ref "J12") (pin "2") (pinfunction "S_2") (pintype "passive"))
    )
    (net (code "13") (name "GND") (class "Default")
      (node (ref "C10") (pin "2") (pinfunction "2_2") (pintype "passive"))
      (node (ref "C11") (pin "2") (pinfunction "2_2") (pintype "passive"))
      (node (ref "C12") (pin "2") (pinfunction "2_2") (pintype "passive"))
      (node (ref "C13") (pin "2") (pinfunction "2_2") (pintype "passive"))
      (node (ref "C14") (pin "2") (pinfunction "2_2") (pintype "passive"))
      (node (ref "C3") (pin "-") (pinfunction "-_-") (pintype "passive"))
      (node (ref "C33") (pin "1") (pinfunction "1_1") (pintype "passive"))
      (node (ref "C34") (pin "1") (pinfunction "1_1") (pintype "passive"))
      (node (ref "C35") (pin "2") (pinfunction "2_2") (pintype "passive"))
      (node (ref "C36") (pin "2") (pinfunction "2_2") (pintype "passive"))
      (node (ref "C4") (pin "2") (pinfunction "2_2") (pintype "passive"))
      (node (ref "C9") (pin "-") (pinfunction "-_-") (pintype "passive"))
      (node (ref "CN1") (pin "3") (pinfunction "3_3") (pintype "passive"))
      (node (ref "IC1") (pin "1") (pinfunction "ADJ_1") (pintype "input"))
      (node (ref "IC2") (pin "16") (pinfunction "AVSS_16") (pintype "passive"))
      (node (ref "IC2") (pin "29") (pinfunction "VSS_29") (pintype "passive"))
      (node (ref "IC2") (pin "39") (pinfunction "VSS_39") (pintype "passive"))
      (node (ref "IC2") (pin "6") (pinfunction "VSS_6") (pintype "passive"))
      (node (ref "IC4") (pin "6") (pinfunction "GND_6") (pintype "power_in"))
      (node (ref "IC5") (pin "6") (pinfunction "GND_6") (pintype "power_in"))
      (node (ref "IC6") (pin "6") (pinfunction "GND_6") (pintype "power_in"))
      (node (ref "IC7") (pin "1") (pinfunction "GND_1") (pintype "passive"))
      (node (ref "IC7") (pin "14") (pinfunction "GND_14") (pintype "passive"))
      (node (ref "IC7") (pin "15") (pinfunction "GND_15") (pintype "passive"))
      (node (ref "IC7") (pin "28") (pinfunction "GND_28") (pintype "passive"))
      (node (ref "IC8") (pin "10") (pinfunction "T2IN_10") (pintype "input"))
      (node (ref "IC8") (pin "15") (pinfunction "GND_15") (pintype "power_in"))
      (node (ref "IC8") (pin "8") (pinfunction "R2IN_8") (pintype "input"))
      (node (ref "IC9") (pin "1") (pinfunction "VSS_1") (pintype "power_in"))
      (node (ref "IC9") (pin "16") (pinfunction "A0_16") (pintype "bidirectional"))
      (node (ref "IC9") (pin "17") (pinfunction "A1_17") (pintype "bidirectional"))
      (node (ref "IC9") (pin "18") (pinfunction "A2_18") (pintype "bidirectional"))
      (node (ref "IC9") (pin "19") (pinfunction "VSS2_19") (pintype "power_in"))
      (node (ref "IC9") (pin "8") (pinfunction "VSS1_8") (pintype "power_in"))
      (node (ref "J12") (pin "1") (pinfunction "S_1") (pintype "passive"))
      (node (ref "J13") (pin "3") (pinfunction "S_3") (pintype "passive"))
      (node (ref "R10") (pin "1") (pinfunction "1_1") (pintype "passive"))
      (node (ref "R11") (pin "2") (pinfunction "2_2") (pintype "passive"))
      (node (ref "R18") (pin "2") (pinfunction "2_2") (pintype "passive"))
      (node (ref "R20") (pin "2") (pinfunction "2_2") (pintype "passive"))
      (node (ref "R22") (pin "2") (pinfunction "2_2") (pintype "passive"))
      (node (ref "R3") (pin "1") (pinfunction "1_1") (pintype "passive"))
      (node (ref "R4") (pin "1") (pinfunction "1_1") (pintype "passive"))
      (node (ref "S1") (pin "3") (pinfunction "P_3") (pintype "passive"))
      (node (ref "S1") (pin "4") (pinfunction "P1_4") (pintype "passive"))
      (node (ref "SV1") (pin "1") (pinfunction "1_1") (pintype "passive"))
      (node (ref "SV1") (pin "4") (pinfunction "4_4") (pintype "passive"))
    )
    (net (code "14") (name "GNDIO") (class "Default")
      (node (ref "C1") (pin "-") (pinfunction "-_-") (pintype "passive"))
      (node (ref "C2") (pin "2") (pinfunction "2_2") (pintype "passive"))
      (node (ref "C5") (pin "-") (pinfunction "-_-") (pintype "passive"))
      (node (ref "C6") (pin "2") (pinfunction "2_2") (pintype "passive"))
      (node (ref "IC3") (pin "3") (pinfunction "GND_3") (pintype "power_in"))
      (node (ref "J10") (pin "1") (pinfunction "S_1") (pintype "passive"))
      (node (ref "J11") (pin "1") (pinfunction "S_1") (pintype "passive"))
      (node (ref "J26") (pin "1") (pinfunction "S_1") (pintype "passive"))
      (node (ref "J27") (pin "1") (pinfunction "S_1") (pintype "passive"))
      (node (ref "J28") (pin "1") (pinfunction "S_1") (pintype "passive"))
      (node (ref "J29") (pin "1") (pinfunction "S_1") (pintype "passive"))
      (node (ref "J30") (pin "1") (pinfunction "S_1") (pintype "passive"))
      (node (ref "J31") (pin "1") (pinfunction "S_1") (pintype "passive"))
      (node (ref "J32") (pin "1") (pinfunction "S_1") (pintype "passive"))
      (node (ref "J33") (pin "1") (pinfunction "S_1") (pintype "passive"))
      (node (ref "J34") (pin "1") (pinfunction "S_1") (pintype "passive"))
      (node (ref "J35") (pin "1") (pinfunction "S_1") (pintype "passive"))
      (node (ref "J36") (pin "1") (pinfunction "S_1") (pintype "passive"))
      (node (ref "J37") (pin "1") (pinfunction "S_1") (pintype "passive"))
      (node (ref "J38") (pin "1") (pinfunction "S_1") (pintype "passive"))
      (node (ref "J39") (pin "1") (pinfunction "S_1") (pintype "passive"))
      (node (ref "J40") (pin "1") (pinfunction "S_1") (pintype "passive"))
      (node (ref "J41") (pin "1") (pinfunction "S_1") (pintype "passive"))
      (node (ref "J6") (pin "1") (pinfunction "S_1") (pintype "passive"))
      (node (ref "J7") (pin "1") (pinfunction "S_1") (pintype "passive"))
      (node (ref "J8") (pin "1") (pinfunction "S_1") (pintype "passive"))
      (node (ref "J9") (pin "1") (pinfunction "S_1") (pintype "passive"))
      (node (ref "R1") (pin "1") (pinfunction "1_1") (pintype "passive"))
      (node (ref "R2") (pin "1") (pinfunction "1_1") (pintype "passive"))
      (node (ref "R3") (pin "2") (pinfunction "2_2") (pintype "passive"))
      (node (ref "R5") (pin "1") (pinfunction "1_1") (pintype "passive"))
      (node (ref "R6") (pin "1") (pinfunction "1_1") (pintype "passive"))
      (node (ref "SJ1") (pin "1") (pinfunction "1_1") (pintype "passive"))
      (node (ref "SJ10") (pin "1") (pinfunction "1_1") (pintype "passive"))
      (node (ref "SJ11") (pin "1") (pinfunction "1_1") (pintype "passive"))
      (node (ref "SJ12") (pin "1") (pinfunction "1_1") (pintype "passive"))
      (node (ref "SJ13") (pin "1") (pinfunction "1_1") (pintype "passive"))
      (node (ref "SJ14") (pin "1") (pinfunction "1_1") (pintype "passive"))
      (node (ref "SJ15") (pin "1") (pinfunction "1_1") (pintype "passive"))
      (node (ref "SJ16") (pin "1") (pinfunction "1_1") (pintype "passive"))
      (node (ref "SJ17") (pin "1") (pinfunction "1_1") (pintype "passive"))
      (node (ref "SJ18") (pin "1") (pinfunction "1_1") (pintype "passive"))
      (node (ref "SJ19") (pin "1") (pinfunction "1_1") (pintype "passive"))
      (node (ref "SJ2") (pin "1") (pinfunction "1_1") (pintype "passive"))
      (node (ref "SJ3") (pin "1") (pinfunction "1_1") (pintype "passive"))
      (node (ref "SJ4") (pin "1") (pinfunction "1_1") (pintype "passive"))
      (node (ref "SJ5") (pin "1") (pinfunction "1_1") (pintype "passive"))
      (node (ref "SJ6") (pin "1") (pinfunction "1_1") (pintype "passive"))
      (node (ref "SJ7") (pin "1") (pinfunction "1_1") (pintype "passive"))
      (node (ref "SJ8") (pin "1") (pinfunction "1_1") (pintype "passive"))
      (node (ref "SJ9") (pin "1") (pinfunction "1_1") (pintype "passive"))
    )
    (net (code "15") (name "GND_SERVO_5V") (class "Default")
      (node (ref "J1") (pin "1") (pinfunction "S_1") (pintype "passive"))
      (node (ref "J2") (pin "1") (pinfunction "S_1") (pintype "passive"))
      (node (ref "J3") (pin "1") (pinfunction "S_1") (pintype "passive"))
      (node (ref "J4") (pin "1") (pinfunction "S_1") (pintype "passive"))
      (node (ref "R1") (pin "2") (pinfunction "2_2") (pintype "passive"))
      (node (ref "X1") (pin "1") (pinfunction "KL_1") (pintype "passive"))
    )
    (net (code "16") (name "GND_SERVO_12V") (class "Default")
      (node (ref "J5") (pin "1") (pinfunction "S_1") (pintype "passive"))
      (node (ref "R5") (pin "2") (pinfunction "2_2") (pintype "passive"))
      (node (ref "X2") (pin "1") (pinfunction "KL_1") (pintype "passive"))
    )
    (net (code "17") (name "GP0_0") (class "Default")
      (node (ref "IC9") (pin "21") (pinfunction "GP0_0_21") (pintype "bidirectional"))
      (node (ref "R24") (pin "2") (pinfunction "2_2") (pintype "passive"))
      (node (ref "SJ4") (pin "2") (pinfunction "2_2") (pintype "passive"))
    )
    (net (code "18") (name "GP0_1") (class "Default")
      (node (ref "IC9") (pin "22") (pinfunction "GP0_1_22") (pintype "bidirectional"))
      (node (ref "R25") (pin "2") (pinfunction "2_2") (pintype "passive"))
      (node (ref "SJ5") (pin "2") (pinfunction "2_2") (pintype "passive"))
    )
    (net (code "19") (name "GP0_2") (class "Default")
      (node (ref "IC9") (pin "23") (pinfunction "GP0_2_23") (pintype "bidirectional"))
      (node (ref "R26") (pin "2") (pinfunction "2_2") (pintype "passive"))
      (node (ref "SJ6") (pin "2") (pinfunction "2_2") (pintype "passive"))
    )
    (net (code "20") (name "GP0_3") (class "Default")
      (node (ref "IC9") (pin "24") (pinfunction "GP0_3_24") (pintype "bidirectional"))
      (node (ref "R27") (pin "2") (pinfunction "2_2") (pintype "passive"))
      (node (ref "SJ7") (pin "2") (pinfunction "2_2") (pintype "passive"))
    )
    (net (code "21") (name "GP0_4") (class "Default")
      (node (ref "IC9") (pin "25") (pinfunction "GP0_4_25") (pintype "bidirectional"))
      (node (ref "R28") (pin "2") (pinfunction "2_2") (pintype "passive"))
      (node (ref "SJ8") (pin "2") (pinfunction "2_2") (pintype "passive"))
    )
    (net (code "22") (name "GP0_5") (class "Default")
      (node (ref "IC9") (pin "26") (pinfunction "GP0_5_26") (pintype "bidirectional"))
      (node (ref "R29") (pin "2") (pinfunction "2_2") (pintype "passive"))
      (node (ref "SJ9") (pin "2") (pinfunction "2_2") (pintype "passive"))
    )
    (net (code "23") (name "GP0_6") (class "Default")
      (node (ref "IC9") (pin "27") (pinfunction "GP0_6_27") (pintype "bidirectional"))
      (node (ref "R30") (pin "2") (pinfunction "2_2") (pintype "passive"))
      (node (ref "SJ10") (pin "2") (pinfunction "2_2") (pintype "passive"))
    )
    (net (code "24") (name "GP0_7") (class "Default")
      (node (ref "IC9") (pin "28") (pinfunction "GP0_7_28") (pintype "bidirectional"))
      (node (ref "R31") (pin "2") (pinfunction "2_2") (pintype "passive"))
      (node (ref "SJ11") (pin "2") (pinfunction "2_2") (pintype "passive"))
    )
    (net (code "25") (name "GP1_0") (class "Default")
      (node (ref "IC9") (pin "2") (pinfunction "GP1_0_2") (pintype "bidirectional"))
      (node (ref "R32") (pin "2") (pinfunction "2_2") (pintype "passive"))
      (node (ref "SJ12") (pin "2") (pinfunction "2_2") (pintype "passive"))
    )
    (net (code "26") (name "GP1_1") (class "Default")
      (node (ref "IC9") (pin "3") (pinfunction "GP1_1_3") (pintype "bidirectional"))
      (node (ref "R33") (pin "2") (pinfunction "2_2") (pintype "passive"))
      (node (ref "SJ13") (pin "2") (pinfunction "2_2") (pintype "passive"))
    )
    (net (code "27") (name "GP1_2") (class "Default")
      (node (ref "IC9") (pin "4") (pinfunction "GP1_2_4") (pintype "bidirectional"))
      (node (ref "R34") (pin "2") (pinfunction "2_2") (pintype "passive"))
      (node (ref "SJ14") (pin "2") (pinfunction "2_2") (pintype "passive"))
    )
    (net (code "28") (name "GP1_3") (class "Default")
      (node (ref "IC9") (pin "5") (pinfunction "GP1_3_5") (pintype "bidirectional"))
      (node (ref "R35") (pin "2") (pinfunction "2_2") (pintype "passive"))
      (node (ref "SJ15") (pin "2") (pinfunction "2_2") (pintype "passive"))
    )
    (net (code "29") (name "GP1_4") (class "Default")
      (node (ref "IC9") (pin "7") (pinfunction "GP1_4_7") (pintype "bidirectional"))
      (node (ref "R36") (pin "2") (pinfunction "2_2") (pintype "passive"))
      (node (ref "SJ16") (pin "2") (pinfunction "2_2") (pintype "passive"))
    )
    (net (code "30") (name "GP1_5") (class "Default")
      (node (ref "IC9") (pin "11") (pinfunction "GP1_5_11") (pintype "bidirectional"))
      (node (ref "R37") (pin "2") (pinfunction "2_2") (pintype "passive"))
      (node (ref "SJ17") (pin "2") (pinfunction "2_2") (pintype "passive"))
    )
    (net (code "31") (name "GP1_6") (class "Default")
      (node (ref "IC9") (pin "12") (pinfunction "GP1_6_12") (pintype "bidirectional"))
      (node (ref "R38") (pin "2") (pinfunction "2_2") (pintype "passive"))
      (node (ref "SJ18") (pin "2") (pinfunction "2_2") (pintype "passive"))
    )
    (net (code "32") (name "GP1_7") (class "Default")
      (node (ref "IC9") (pin "13") (pinfunction "GP1_7_13") (pintype "bidirectional"))
      (node (ref "R39") (pin "2") (pinfunction "2_2") (pintype "passive"))
      (node (ref "SJ19") (pin "2") (pinfunction "2_2") (pintype "passive"))
    )
    (net (code "33") (name "I2C_SCL_(5V)") (class "Default")
      (node (ref "IC2") (pin "42") (pinfunction "PGEC3/ASCL1/RP6*/CN24/PMD6/RB6_42") (pintype "passive"))
      (node (ref "IC9") (pin "14") (pinfunction "SCL_14") (pintype "bidirectional"))
      (node (ref "J13") (pin "2") (pinfunction "S_2") (pintype "passive"))
      (node (ref "R8") (pin "1") (pinfunction "1_1") (pintype "passive"))
    )
    (net (code "34") (name "I2C_SDA_(5V)") (class "Default")
      (node (ref "IC2") (pin "41") (pinfunction "PGED3/ASDA1/RP5*/CN27/PMD7/RB5_41") (pintype "passive"))
      (node (ref "IC9") (pin "15") (pinfunction "SDA_15") (pintype "bidirectional"))
      (node (ref "J13") (pin "1") (pinfunction "S_1") (pintype "passive"))
      (node (ref "R9") (pin "1") (pinfunction "1_1") (pintype "passive"))
    )
    (net (code "35") (name "MISO") (class "Default")
      (node (ref "IC2") (pin "3") (pinfunction "PWM2L1/RP23*/CN17/PMA0/RC7_3") (pintype "passive"))
      (node (ref "SV1") (pin "7") (pinfunction "7_7") (pintype "passive"))
    )
    (net (code "36") (name "MOSI") (class "Default")
      (node (ref "IC2") (pin "2") (pinfunction "PWM2H1/RP22*/CN18/PMA1/RC6_2") (pintype "passive"))
      (node (ref "SV1") (pin "6") (pinfunction "6_6") (pintype "passive"))
    )
    (net (code "37") (name "MOT_1_PWM") (class "Default")
      (node (ref "IC2") (pin "14") (pinfunction "PWM1H1/DAC1LP/RTCC/RP14*/CN12/PMWR/RB14_14") (pintype "passive"))
      (node (ref "IC4") (pin "11") (pinfunction "ENABLE_11") (pintype "input"))
    )
    (net (code "38") (name "MOT_1_SIGN1") (class "Default")
      (node (ref "IC2") (pin "19") (pinfunction "AN0/VREF+/CN2/RA0_19") (pintype "passive"))
      (node (ref "IC4") (pin "5") (pinfunction "IN1_5") (pintype "input"))
    )
    (net (code "39") (name "MOT_1_SIGN2") (class "Default")
      (node (ref "IC2") (pin "20") (pinfunction "AN1/VREF-/CN3/RA1_20") (pintype "passive"))
      (node (ref "IC4") (pin "7") (pinfunction "IN2_7") (pintype "input"))
    )
    (net (code "40") (name "MOT_2_PWM") (class "Default")
      (node (ref "IC2") (pin "10") (pinfunction "PWM1H2/DAC1RP/RP12*/CN14/PMD0/RB12_10") (pintype "passive"))
      (node (ref "IC5") (pin "11") (pinfunction "ENABLE_11") (pintype "input"))
    )
    (net (code "41") (name "MOT_2_SIGN1") (class "Default")
      (node (ref "IC2") (pin "13") (pinfunction "TCK/PMA7/RA7_13") (pintype "passive"))
      (node (ref "IC5") (pin "5") (pinfunction "IN1_5") (pintype "input"))
    )
    (net (code "42") (name "MOT_2_SIGN2") (class "Default")
      (node (ref "IC2") (pin "15") (pinfunction "PWM1L1/DAC1LN/RP15*/CN11/PMCS1/RB15_15") (pintype "passive"))
      (node (ref "IC5") (pin "7") (pinfunction "IN2_7") (pintype "input"))
    )
    (net (code "43") (name "MOT_3_PWM") (class "Default")
      (node (ref "IC2") (pin "8") (pinfunction "PGED2/EMCD2/PWM1H3/RP10*/CN16/PMD2/RB10_8") (pintype "passive"))
      (node (ref "IC6") (pin "11") (pinfunction "ENABLE_11") (pintype "input"))
    )
    (net (code "44") (name "MOT_3_SIGN1") (class "Default")
      (node (ref "IC2") (pin "11") (pinfunction "PWM1L2/DAC1RN/RP13*/CN13/PMRD/RB13_11") (pintype "passive"))
      (node (ref "IC6") (pin "5") (pinfunction "IN1_5") (pintype "input"))
    )
    (net (code "45") (name "MOT_3_SIGN2") (class "Default")
      (node (ref "IC2") (pin "12") (pinfunction "TMS/PMA10/RA10_12") (pintype "passive"))
      (node (ref "IC6") (pin "7") (pinfunction "IN2_7") (pintype "input"))
    )
    (net (code "46") (name "Net-(C19-Pad2)") (class "Default")
      (node (ref "C19") (pin "2") (pinfunction "2_2") (pintype "passive"))
      (node (ref "R19") (pin "1") (pinfunction "1_1") (pintype "passive"))
    )
    (net (code "47") (name "Net-(C24-Pad2)") (class "Default")
      (node (ref "C24") (pin "2") (pinfunction "2_2") (pintype "passive"))
      (node (ref "R21") (pin "1") (pinfunction "1_1") (pintype "passive"))
    )
    (net (code "48") (name "Net-(C29-Pad2)") (class "Default")
      (node (ref "C29") (pin "2") (pinfunction "2_2") (pintype "passive"))
      (node (ref "R23") (pin "1") (pinfunction "1_1") (pintype "passive"))
    )
    (net (code "49") (name "Net-(IC2-OSC1{slash}CLKI{slash}CN30{slash}RA2)") (class "Default")
      (node (ref "C13") (pin "1") (pinfunction "1_1") (pintype "passive"))
      (node (ref "IC2") (pin "30") (pinfunction "OSC1/CLKI/CN30/RA2_30") (pintype "passive"))
      (node (ref "Q1") (pin "1") (pinfunction "1_1") (pintype "passive"))
    )
    (net (code "50") (name "Net-(IC2-OSC2{slash}CLKO{slash}CN29{slash}RA3)") (class "Default")
      (node (ref "C14") (pin "1") (pinfunction "1_1") (pintype "passive"))
      (node (ref "IC2") (pin "31") (pinfunction "OSC2/CLKO/CN29/RA3_31") (pintype "passive"))
      (node (ref "Q1") (pin "2") (pinfunction "2_2") (pintype "passive"))
    )
    (net (code "51") (name "Net-(IC2-VCAP{slash}VDDCORE)") (class "Default")
      (node (ref "C9") (pin "+") (pinfunction "+_+") (pintype "passive"))
      (node (ref "IC2") (pin "7") (pinfunction "VCAP/VDDCORE_7") (pintype "passive"))
    )
    (net (code "52") (name "Net-(IC3-I0)") (class "Default")
      (node (ref "IC3") (pin "1") (pinfunction "I0_1") (pintype "input"))
      (node (ref "J11") (pin "3") (pinfunction "S_3") (pintype "passive"))
    )
    (net (code "53") (name "Net-(IC3-I1)") (class "Default")
      (node (ref "IC3") (pin "2") (pinfunction "I1_2") (pintype "input"))
      (node (ref "J11") (pin "4") (pinfunction "S_4") (pintype "passive"))
    )
    (net (code "54") (name "Net-(IC4-CBOOT1)") (class "Default")
      (node (ref "C17") (pin "1") (pinfunction "1_1") (pintype "passive"))
      (node (ref "IC4") (pin "4") (pinfunction "CBOOT1_4") (pintype "input"))
    )
    (net (code "55") (name "Net-(IC4-CBOOT2)") (class "Default")
      (node (ref "C18") (pin "1") (pinfunction "1_1") (pintype "passive"))
      (node (ref "IC4") (pin "8") (pinfunction "CBOOT2_8") (pintype "input"))
    )
    (net (code "56") (name "Net-(IC4-OUT1)") (class "Default")
      (node (ref "C17") (pin "2") (pinfunction "2_2") (pintype "passive"))
      (node (ref "D1") (pin "C") (pinfunction "C_C") (pintype "passive"))
      (node (ref "IC4") (pin "3") (pinfunction "OUT1_3") (pintype "output"))
      (node (ref "R19") (pin "2") (pinfunction "2_2") (pintype "passive"))
      (node (ref "X4") (pin "2") (pinfunction "KL_2") (pintype "passive"))
    )
    (net (code "57") (name "Net-(IC4-OUT2)") (class "Default")
      (node (ref "C18") (pin "2") (pinfunction "2_2") (pintype "passive"))
      (node (ref "C19") (pin "1") (pinfunction "1_1") (pintype "passive"))
      (node (ref "D2") (pin "C") (pinfunction "C_C") (pintype "passive"))
      (node (ref "IC4") (pin "1") (pinfunction "OUT2_1") (pintype "output"))
      (node (ref "X4") (pin "1") (pinfunction "KL_1") (pintype "passive"))
    )
    (net (code "58") (name "Net-(IC4-VREF)") (class "Default")
      (node (ref "C16") (pin "1") (pinfunction "1_1") (pintype "passive"))
      (node (ref "IC4") (pin "9") (pinfunction "VREF_9") (pintype "input"))
    )
    (net (code "59") (name "Net-(IC5-CBOOT1)") (class "Default")
      (node (ref "C22") (pin "1") (pinfunction "1_1") (pintype "passive"))
      (node (ref "IC5") (pin "4") (pinfunction "CBOOT1_4") (pintype "input"))
    )
    (net (code "60") (name "Net-(IC5-CBOOT2)") (class "Default")
      (node (ref "C23") (pin "1") (pinfunction "1_1") (pintype "passive"))
      (node (ref "IC5") (pin "8") (pinfunction "CBOOT2_8") (pintype "input"))
    )
    (net (code "61") (name "Net-(IC5-OUT1)") (class "Default")
      (node (ref "C22") (pin "2") (pinfunction "2_2") (pintype "passive"))
      (node (ref "D3") (pin "C") (pinfunction "C_C") (pintype "passive"))
      (node (ref "IC5") (pin "3") (pinfunction "OUT1_3") (pintype "output"))
      (node (ref "R21") (pin "2") (pinfunction "2_2") (pintype "passive"))
      (node (ref "X5") (pin "2") (pinfunction "KL_2") (pintype "passive"))
    )
    (net (code "62") (name "Net-(IC5-OUT2)") (class "Default")
      (node (ref "C23") (pin "2") (pinfunction "2_2") (pintype "passive"))
      (node (ref "C24") (pin "1") (pinfunction "1_1") (pintype "passive"))
      (node (ref "D4") (pin "C") (pinfunction "C_C") (pintype "passive"))
      (node (ref "IC5") (pin "1") (pinfunction "OUT2_1") (pintype "output"))
      (node (ref "X5") (pin "1") (pinfunction "KL_1") (pintype "passive"))
    )
    (net (code "63") (name "Net-(IC5-VREF)") (class "Default")
      (node (ref "C21") (pin "1") (pinfunction "1_1") (pintype "passive"))
      (node (ref "IC5") (pin "9") (pinfunction "VREF_9") (pintype "input"))
    )
    (net (code "64") (name "Net-(IC6-CBOOT1)") (class "Default")
      (node (ref "C27") (pin "1") (pinfunction "1_1") (pintype "passive"))
      (node (ref "IC6") (pin "4") (pinfunction "CBOOT1_4") (pintype "input"))
    )
    (net (code "65") (name "Net-(IC6-CBOOT2)") (class "Default")
      (node (ref "C28") (pin "1") (pinfunction "1_1") (pintype "passive"))
      (node (ref "IC6") (pin "8") (pinfunction "CBOOT2_8") (pintype "input"))
    )
    (net (code "66") (name "Net-(IC6-OUT1)") (class "Default")
      (node (ref "C27") (pin "2") (pinfunction "2_2") (pintype "passive"))
      (node (ref "D5") (pin "C") (pinfunction "C_C") (pintype "passive"))
      (node (ref "IC6") (pin "3") (pinfunction "OUT1_3") (pintype "output"))
      (node (ref "R23") (pin "2") (pinfunction "2_2") (pintype "passive"))
      (node (ref "X6") (pin "2") (pinfunction "KL_2") (pintype "passive"))
    )
    (net (code "67") (name "Net-(IC6-OUT2)") (class "Default")
      (node (ref "C28") (pin "2") (pinfunction "2_2") (pintype "passive"))
      (node (ref "C29") (pin "1") (pinfunction "1_1") (pintype "passive"))
      (node (ref "D6") (pin "C") (pinfunction "C_C") (pintype "passive"))
      (node (ref "IC6") (pin "1") (pinfunction "OUT2_1") (pintype "output"))
      (node (ref "X6") (pin "1") (pinfunction "KL_1") (pintype "passive"))
    )
    (net (code "68") (name "Net-(IC6-VREF)") (class "Default")
      (node (ref "C26") (pin "1") (pinfunction "1_1") (pintype "passive"))
      (node (ref "IC6") (pin "9") (pinfunction "VREF_9") (pintype "input"))
    )
    (net (code "69") (name "Net-(IC7-NCTS)") (class "Default")
      (node (ref "IC7") (pin "10") (pinfunction "NCTS_10") (pintype "passive"))
      (node (ref "IC7") (pin "5") (pinfunction "NRTS_5") (pintype "passive"))
    )
    (net (code "70") (name "Net-(IC8A-C1+)") (class "Default")
      (node (ref "C30") (pin "2") (pinfunction "2_2") (pintype "passive"))
      (node (ref "IC8") (pin "1") (pinfunction "C1+_1") (pintype "bidirectional"))
    )
    (net (code "71") (name "Net-(IC8A-C1-)") (class "Default")
      (node (ref "C30") (pin "1") (pinfunction "1_1") (pintype "passive"))
      (node (ref "IC8") (pin "3") (pinfunction "C1-_3") (pintype "bidirectional"))
    )
    (net (code "72") (name "Net-(IC8A-C2+)") (class "Default")
      (node (ref "C31") (pin "2") (pinfunction "2_2") (pintype "passive"))
      (node (ref "IC8") (pin "4") (pinfunction "C2+_4") (pintype "bidirectional"))
    )
    (net (code "73") (name "Net-(IC8A-C2-)") (class "Default")
      (node (ref "C31") (pin "1") (pinfunction "1_1") (pintype "passive"))
      (node (ref "IC8") (pin "5") (pinfunction "C2-_5") (pintype "bidirectional"))
    )
    (net (code "74") (name "Net-(IC8A-V+)") (class "Default")
      (node (ref "C32") (pin "1") (pinfunction "1_1") (pintype "passive"))
      (node (ref "IC8") (pin "2") (pinfunction "V+_2") (pintype "bidirectional"))
    )
    (net (code "75") (name "Net-(IC8A-V-)") (class "Default")
      (node (ref "C33") (pin "2") (pinfunction "2_2") (pintype "passive"))
      (node (ref "IC8") (pin "6") (pinfunction "V-_6") (pintype "bidirectional"))
    )
    (net (code "76") (name "Net-(IC9-CLK)") (class "Default")
      (node (ref "C36") (pin "1") (pinfunction "1_1") (pintype "passive"))
      (node (ref "IC9") (pin "9") (pinfunction "CLK_9") (pintype "bidirectional"))
      (node (ref "R40") (pin "1") (pinfunction "1_1") (pintype "passive"))
    )
    (net (code "77") (name "Net-(J6C-S)") (class "Default")
      (node (ref "J6") (pin "3") (pinfunction "S_3") (pintype "passive"))
      (node (ref "R15") (pin "1") (pinfunction "1_1") (pintype "passive"))
    )
    (net (code "78") (name "Net-(J7C-S)") (class "Default")
      (node (ref "J7") (pin "3") (pinfunction "S_3") (pintype "passive"))
      (node (ref "R16") (pin "1") (pinfunction "1_1") (pintype "passive"))
    )
    (net (code "79") (name "Net-(J8C-S)") (class "Default")
      (node (ref "J8") (pin "3") (pinfunction "S_3") (pintype "passive"))
      (node (ref "R17") (pin "1") (pinfunction "1_1") (pintype "passive"))
    )
    (net (code "80") (name "Net-(J26C-S)") (class "Default")
      (node (ref "J26") (pin "3") (pinfunction "S_3") (pintype "passive"))
      (node (ref "R24") (pin "1") (pinfunction "1_1") (pintype "passive"))
    )
    (net (code "81") (name "Net-(J27C-S)") (class "Default")
      (node (ref "J27") (pin "3") (pinfunction "S_3") (pintype "passive"))
      (node (ref "R25") (pin "1") (pinfunction "1_1") (pintype "passive"))
    )
    (net (code "82") (name "Net-(J28C-S)") (class "Default")
      (node (ref "J28") (pin "3") (pinfunction "S_3") (pintype "passive"))
      (node (ref "R26") (pin "1") (pinfunction "1_1") (pintype "passive"))
    )
    (net (code "83") (name "Net-(J29C-S)") (class "Default")
      (node (ref "J29") (pin "3") (pinfunction "S_3") (pintype "passive"))
      (node (ref "R27") (pin "1") (pinfunction "1_1") (pintype "passive"))
    )
    (net (code "84") (name "Net-(J30C-S)") (class "Default")
      (node (ref "J30") (pin "3") (pinfunction "S_3") (pintype "passive"))
      (node (ref "R28") (pin "1") (pinfunction "1_1") (pintype "passive"))
    )
    (net (code "85") (name "Net-(J31C-S)") (class "Default")
      (node (ref "J31") (pin "3") (pinfunction "S_3") (pintype "passive"))
      (node (ref "R29") (pin "1") (pinfunction "1_1") (pintype "passive"))
    )
    (net (code "86") (name "Net-(J32C-S)") (class "Default")
      (node (ref "J32") (pin "3") (pinfunction "S_3") (pintype "passive"))
      (node (ref "R30") (pin "1") (pinfunction "1_1") (pintype "passive"))
    )
    (net (code "87") (name "Net-(J33C-S)") (class "Default")
      (node (ref "J33") (pin "3") (pinfunction "S_3") (pintype "passive"))
      (node (ref "R31") (pin "1") (pinfunction "1_1") (pintype "passive"))
    )
    (net (code "88") (name "Net-(J34C-S)") (class "Default")
      (node (ref "J34") (pin "3") (pinfunction "S_3") (pintype "passive"))
      (node (ref "R32") (pin "1") (pinfunction "1_1") (pintype "passive"))
    )
    (net (code "89") (name "Net-(J35C-S)") (class "Default")
      (node (ref "J35") (pin "3") (pinfunction "S_3") (pintype "passive"))
      (node (ref "R33") (pin "1") (pinfunction "1_1") (pintype "passive"))
    )
    (net (code "90") (name "Net-(J36C-S)") (class "Default")
      (node (ref "J36") (pin "3") (pinfunction "S_3") (pintype "passive"))
      (node (ref "R34") (pin "1") (pinfunction "1_1") (pintype "passive"))
    )
    (net (code "91") (name "Net-(J37C-S)") (class "Default")
      (node (ref "J37") (pin "3") (pinfunction "S_3") (pintype "passive"))
      (node (ref "R35") (pin "1") (pinfunction "1_1") (pintype "passive"))
    )
    (net (code "92") (name "Net-(J38C-S)") (class "Default")
      (node (ref "J38") (pin "3") (pinfunction "S_3") (pintype "passive"))
      (node (ref "R36") (pin "1") (pinfunction "1_1") (pintype "passive"))
    )
    (net (code "93") (name "Net-(J39C-S)") (class "Default")
      (node (ref "J39") (pin "3") (pinfunction "S_3") (pintype "passive"))
      (node (ref "R37") (pin "1") (pinfunction "1_1") (pintype "passive"))
    )
    (net (code "94") (name "Net-(J40C-S)") (class "Default")
      (node (ref "J40") (pin "3") (pinfunction "S_3") (pintype "passive"))
      (node (ref "R38") (pin "1") (pinfunction "1_1") (pintype "passive"))
    )
    (net (code "95") (name "Net-(J41C-S)") (class "Default")
      (node (ref "J41") (pin "3") (pinfunction "S_3") (pintype "passive"))
      (node (ref "R39") (pin "1") (pinfunction "1_1") (pintype "passive"))
    )
    (net (code "96") (name "Net-(LED1-PadC)") (class "Default")
      (node (ref "LED1") (pin "C") (pinfunction "C_C") (pintype "passive"))
      (node (ref "R2") (pin "2") (pinfunction "2_2") (pintype "passive"))
    )
    (net (code "97") (name "Net-(LED2-PadC)") (class "Default")
      (node (ref "LED2") (pin "C") (pinfunction "C_C") (pintype "passive"))
      (node (ref "R4") (pin "2") (pinfunction "2_2") (pintype "passive"))
    )
    (net (code "98") (name "Net-(LED3-PadC)") (class "Default")
      (node (ref "LED3") (pin "C") (pinfunction "C_C") (pintype "passive"))
      (node (ref "R6") (pin "2") (pinfunction "2_2") (pintype "passive"))
    )
    (net (code "99") (name "Net-(LED4-PadC)") (class "Default")
      (node (ref "LED4") (pin "C") (pinfunction "C_C") (pintype "passive"))
      (node (ref "R7") (pin "2") (pinfunction "2_2") (pintype "passive"))
    )
    (net (code "100") (name "Net-(LED5-PadC)") (class "Default")
      (node (ref "LED5") (pin "C") (pinfunction "C_C") (pintype "passive"))
      (node (ref "R13") (pin "2") (pinfunction "2_2") (pintype "passive"))
    )
    (net (code "101") (name "PGEC") (class "Default")
      (node (ref "CN1") (pin "5") (pinfunction "5_5") (pintype "passive"))
      (node (ref "IC2") (pin "22") (pinfunction "PGEC1/AN3/C2IN+/RP1*/CN5/RB1_22") (pintype "passive"))
      (node (ref "R11") (pin "1") (pinfunction "1_1") (pintype "passive"))
    )
    (net (code "102") (name "PGED") (class "Default")
      (node (ref "CN1") (pin "4") (pinfunction "4_4") (pintype "passive"))
      (node (ref "IC2") (pin "21") (pinfunction "PGED1/AN2/C2IN-/RP0*/CN4/RB0_21") (pintype "passive"))
      (node (ref "R10") (pin "2") (pinfunction "2_2") (pintype "passive"))
    )
    (net (code "103") (name "RF24_CE") (class "Default")
      (node (ref "IC2") (pin "34") (pinfunction "SOSCO/T1CK/CN0/RA4_34") (pintype "passive"))
      (node (ref "R13") (pin "1") (pinfunction "1_1") (pintype "passive"))
      (node (ref "SV1") (pin "3") (pinfunction "3_3") (pintype "passive"))
    )
    (net (code "104") (name "RST") (class "Default")
      (node (ref "CN1") (pin "1") (pinfunction "1_1") (pintype "passive"))
      (node (ref "IC2") (pin "18") (pinfunction "MCLR_18") (pintype "passive"))
      (node (ref "R12") (pin "1") (pinfunction "1_1") (pintype "passive"))
      (node (ref "S1") (pin "1") (pinfunction "S_1") (pintype "passive"))
      (node (ref "S1") (pin "2") (pinfunction "S1_2") (pintype "passive"))
    )
    (net (code "105") (name "SCK") (class "Default")
      (node (ref "IC2") (pin "4") (pinfunction "RP24*/CN20/PMA5/RC8_4") (pintype "passive"))
      (node (ref "SV1") (pin "5") (pinfunction "5_5") (pintype "passive"))
    )
    (net (code "106") (name "SENSOR_1") (class "Default")
      (node (ref "IC2") (pin "5") (pinfunction "RP25*/CN19/PMA6/RC9_5") (pintype "passive"))
      (node (ref "R15") (pin "2") (pinfunction "2_2") (pintype "passive"))
      (node (ref "SJ1") (pin "2") (pinfunction "2_2") (pintype "passive"))
    )
    (net (code "107") (name "SENSOR_2") (class "Default")
      (node (ref "IC2") (pin "23") (pinfunction "AN4/C1IN-/RP2*/CN6/RB2_23") (pintype "passive"))
      (node (ref "R16") (pin "2") (pinfunction "2_2") (pintype "passive"))
      (node (ref "SJ2") (pin "2") (pinfunction "2_2") (pintype "passive"))
    )
    (net (code "108") (name "SENSOR_3") (class "Default")
      (node (ref "IC2") (pin "32") (pinfunction "TDO/PMA8/RA8_32") (pintype "passive"))
      (node (ref "R17") (pin "2") (pinfunction "2_2") (pintype "passive"))
      (node (ref "SJ3") (pin "2") (pinfunction "2_2") (pintype "passive"))
    )
    (net (code "109") (name "SERVO_1_PWM") (class "Default")
      (node (ref "IC2") (pin "27") (pinfunction "AN8/CVREF/RP18*/PMA2/CN10/RC2_27") (pintype "passive"))
      (node (ref "J1") (pin "3") (pinfunction "S_3") (pintype "passive"))
    )
    (net (code "110") (name "SERVO_2_PWM") (class "Default")
      (node (ref "IC2") (pin "26") (pinfunction "AN7/DAC1LM/RP17*/CN9/RC1_26") (pintype "passive"))
      (node (ref "J2") (pin "3") (pinfunction "S_3") (pintype "passive"))
    )
    (net (code "111") (name "SERVO_3_PWM") (class "Default")
      (node (ref "IC2") (pin "25") (pinfunction "AN6/DAC1RM/RP16*/CN8/RC0_25") (pintype "passive"))
      (node (ref "J3") (pin "3") (pinfunction "S_3") (pintype "passive"))
    )
    (net (code "112") (name "SERVO_4_PWM") (class "Default")
      (node (ref "IC2") (pin "24") (pinfunction "AN5/C1IN+/RP3*/CN7/RB3_24") (pintype "passive"))
      (node (ref "J4") (pin "3") (pinfunction "S_3") (pintype "passive"))
    )
    (net (code "113") (name "SERVO_AX12_UART") (class "Default")
      (node (ref "IC2") (pin "1") (pinfunction "SDA1/RP9*/CN21/PMD3/RB9_1") (pintype "passive"))
      (node (ref "J5") (pin "3") (pinfunction "S_3") (pintype "passive"))
      (node (ref "R14") (pin "1") (pinfunction "1_1") (pintype "passive"))
    )
    (net (code "114") (name "TO_RX_RS232_M") (class "Default")
      (node (ref "IC8") (pin "14") (pinfunction "T1OUT_14") (pintype "output"))
      (node (ref "J12") (pin "3") (pinfunction "S_3") (pintype "passive"))
    )
    (net (code "115") (name "UART_RX") (class "Default")
      (node (ref "IC2") (pin "44") (pinfunction "SCL1/RP8*/CN22/PMD4/RB8_44") (pintype "passive"))
      (node (ref "IC7") (pin "26") (pinfunction "TXD_26") (pintype "passive"))
    )
    (net (code "116") (name "UART_RX_BYPASS") (class "Default")
      (node (ref "IC7") (pin "20") (pinfunction "PIO4_20") (pintype "passive"))
      (node (ref "IC8") (pin "12") (pinfunction "R1OUT_12") (pintype "output"))
    )
    (net (code "117") (name "UART_TX") (class "Default")
      (node (ref "IC2") (pin "43") (pinfunction "INT0/RP7*/CN23/PMD5/RB7_43") (pintype "passive"))
      (node (ref "IC7") (pin "6") (pinfunction "RXD_6") (pintype "passive"))
    )
    (net (code "118") (name "UART_TX_BYPASS") (class "Default")
      (node (ref "IC7") (pin "19") (pinfunction "PIO7_19") (pintype "passive"))
      (node (ref "IC8") (pin "11") (pinfunction "T1IN_11") (pintype "input"))
    )
    (net (code "119") (name "VCC_SERVO_5V") (class "Default")
      (node (ref "F1") (pin "1") (pinfunction "1_1") (pintype "passive"))
      (node (ref "J1") (pin "2") (pinfunction "S_2") (pintype "passive"))
      (node (ref "J2") (pin "2") (pinfunction "S_2") (pintype "passive"))
      (node (ref "J3") (pin "2") (pinfunction "S_2") (pintype "passive"))
      (node (ref "J4") (pin "2") (pinfunction "S_2") (pintype "passive"))
      (node (ref "X1") (pin "2") (pinfunction "KL_2") (pintype "passive"))
    )
    (net (code "120") (name "VCC_SERVO_12V") (class "Default")
      (node (ref "C5") (pin "+") (pinfunction "+_+") (pintype "passive"))
      (node (ref "C6") (pin "1") (pinfunction "1_1") (pintype "passive"))
      (node (ref "F2") (pin "1") (pinfunction "1_1") (pintype "passive"))
      (node (ref "J5") (pin "2") (pinfunction "S_2") (pintype "passive"))
      (node (ref "X2") (pin "2") (pinfunction "KL_2") (pintype "passive"))
    )
    (net (code "121") (name "unconnected-(IC7-AIO-Pad27)") (class "Default")
      (node (ref "IC7") (pin "27") (pinfunction "AIO_27") (pintype "passive"))
    )
    (net (code "122") (name "unconnected-(IC7-MISO-Pad23)") (class "Default")
      (node (ref "IC7") (pin "23") (pinfunction "MISO_23") (pintype "passive"))
    )
    (net (code "123") (name "unconnected-(IC7-MOSI-Pad24)") (class "Default")
      (node (ref "IC7") (pin "24") (pinfunction "MOSI_24") (pintype "passive"))
    )
    (net (code "124") (name "unconnected-(IC7-NCSB-Pad21)") (class "Default")
      (node (ref "IC7") (pin "21") (pinfunction "NCSB_21") (pintype "passive"))
    )
    (net (code "125") (name "unconnected-(IC7-PCMC-Pad12)") (class "Default")
      (node (ref "IC7") (pin "12") (pinfunction "PCMC_12") (pintype "passive"))
    )
    (net (code "126") (name "unconnected-(IC7-PCMI-Pad11)") (class "Default")
      (node (ref "IC7") (pin "11") (pinfunction "PCMI_11") (pintype "passive"))
    )
    (net (code "127") (name "unconnected-(IC7-PCMO-Pad7)") (class "Default")
      (node (ref "IC7") (pin "7") (pinfunction "PCMO_7") (pintype "passive"))
    )
    (net (code "128") (name "unconnected-(IC7-PCMS-Pad13)") (class "Default")
      (node (ref "IC7") (pin "13") (pinfunction "PCMS_13") (pintype "passive"))
    )
    (net (code "129") (name "unconnected-(IC7-PIO2-Pad3)") (class "Default")
      (node (ref "IC7") (pin "3") (pinfunction "PIO2_3") (pintype "passive"))
    )
    (net (code "130") (name "unconnected-(IC7-PIO3-Pad4)") (class "Default")
      (node (ref "IC7") (pin "4") (pinfunction "PIO3_4") (pintype "passive"))
    )
    (net (code "131") (name "unconnected-(IC7-PIO5-Pad25)") (class "Default")
      (node (ref "IC7") (pin "25") (pinfunction "PIO5_25") (pintype "passive"))
    )
    (net (code "132") (name "unconnected-(IC7-PIO6-Pad18)") (class "Default")
      (node (ref "IC7") (pin "18") (pinfunction "PIO6_18") (pintype "passive"))
    )
    (net (code "133") (name "unconnected-(IC7-SCLK-Pad22)") (class "Default")
      (node (ref "IC7") (pin "22") (pinfunction "SCLK_22") (pintype "passive"))
    )
    (net (code "134") (name "unconnected-(IC7-USB_D+-Pad8)") (class "Default")
      (node (ref "IC7") (pin "8") (pinfunction "USB_D+_8") (pintype "passive"))
    )
    (net (code "135") (name "unconnected-(IC7-USB_D--Pad9)") (class "Default")
      (node (ref "IC7") (pin "9") (pinfunction "USB_D-_9") (pintype "passive"))
    )
    (net (code "136") (name "unconnected-(IC8A-R2OUT-Pad9)") (class "Default")
      (node (ref "IC8") (pin "9") (pinfunction "R2OUT_9") (pintype "output"))
    )
    (net (code "137") (name "unconnected-(IC8A-T2OUT-Pad7)") (class "Default")
      (node (ref "IC8") (pin "7") (pinfunction "T2OUT_7") (pintype "output"))
    )
    (net (code "138") (name "unconnected-(IC9-INT-Pad6)") (class "Default")
      (node (ref "IC9") (pin "6") (pinfunction "INT_6") (pintype "bidirectional"))
    )
    (net (code "139") (name "unconnected-(IC9-TP-Pad10)") (class "Default")
      (node (ref "IC9") (pin "10") (pinfunction "TP_10") (pintype "bidirectional"))
    )
    (net (code "140") (name "unconnected-(SV1-Pad8)") (class "Default")
      (node (ref "SV1") (pin "8") (pinfunction "8_8") (pintype "passive"))
    )
  )
)
